# uOsc_2_board_2_v2_0.net
KiCad netlist of a schematic drawn in EAGLE
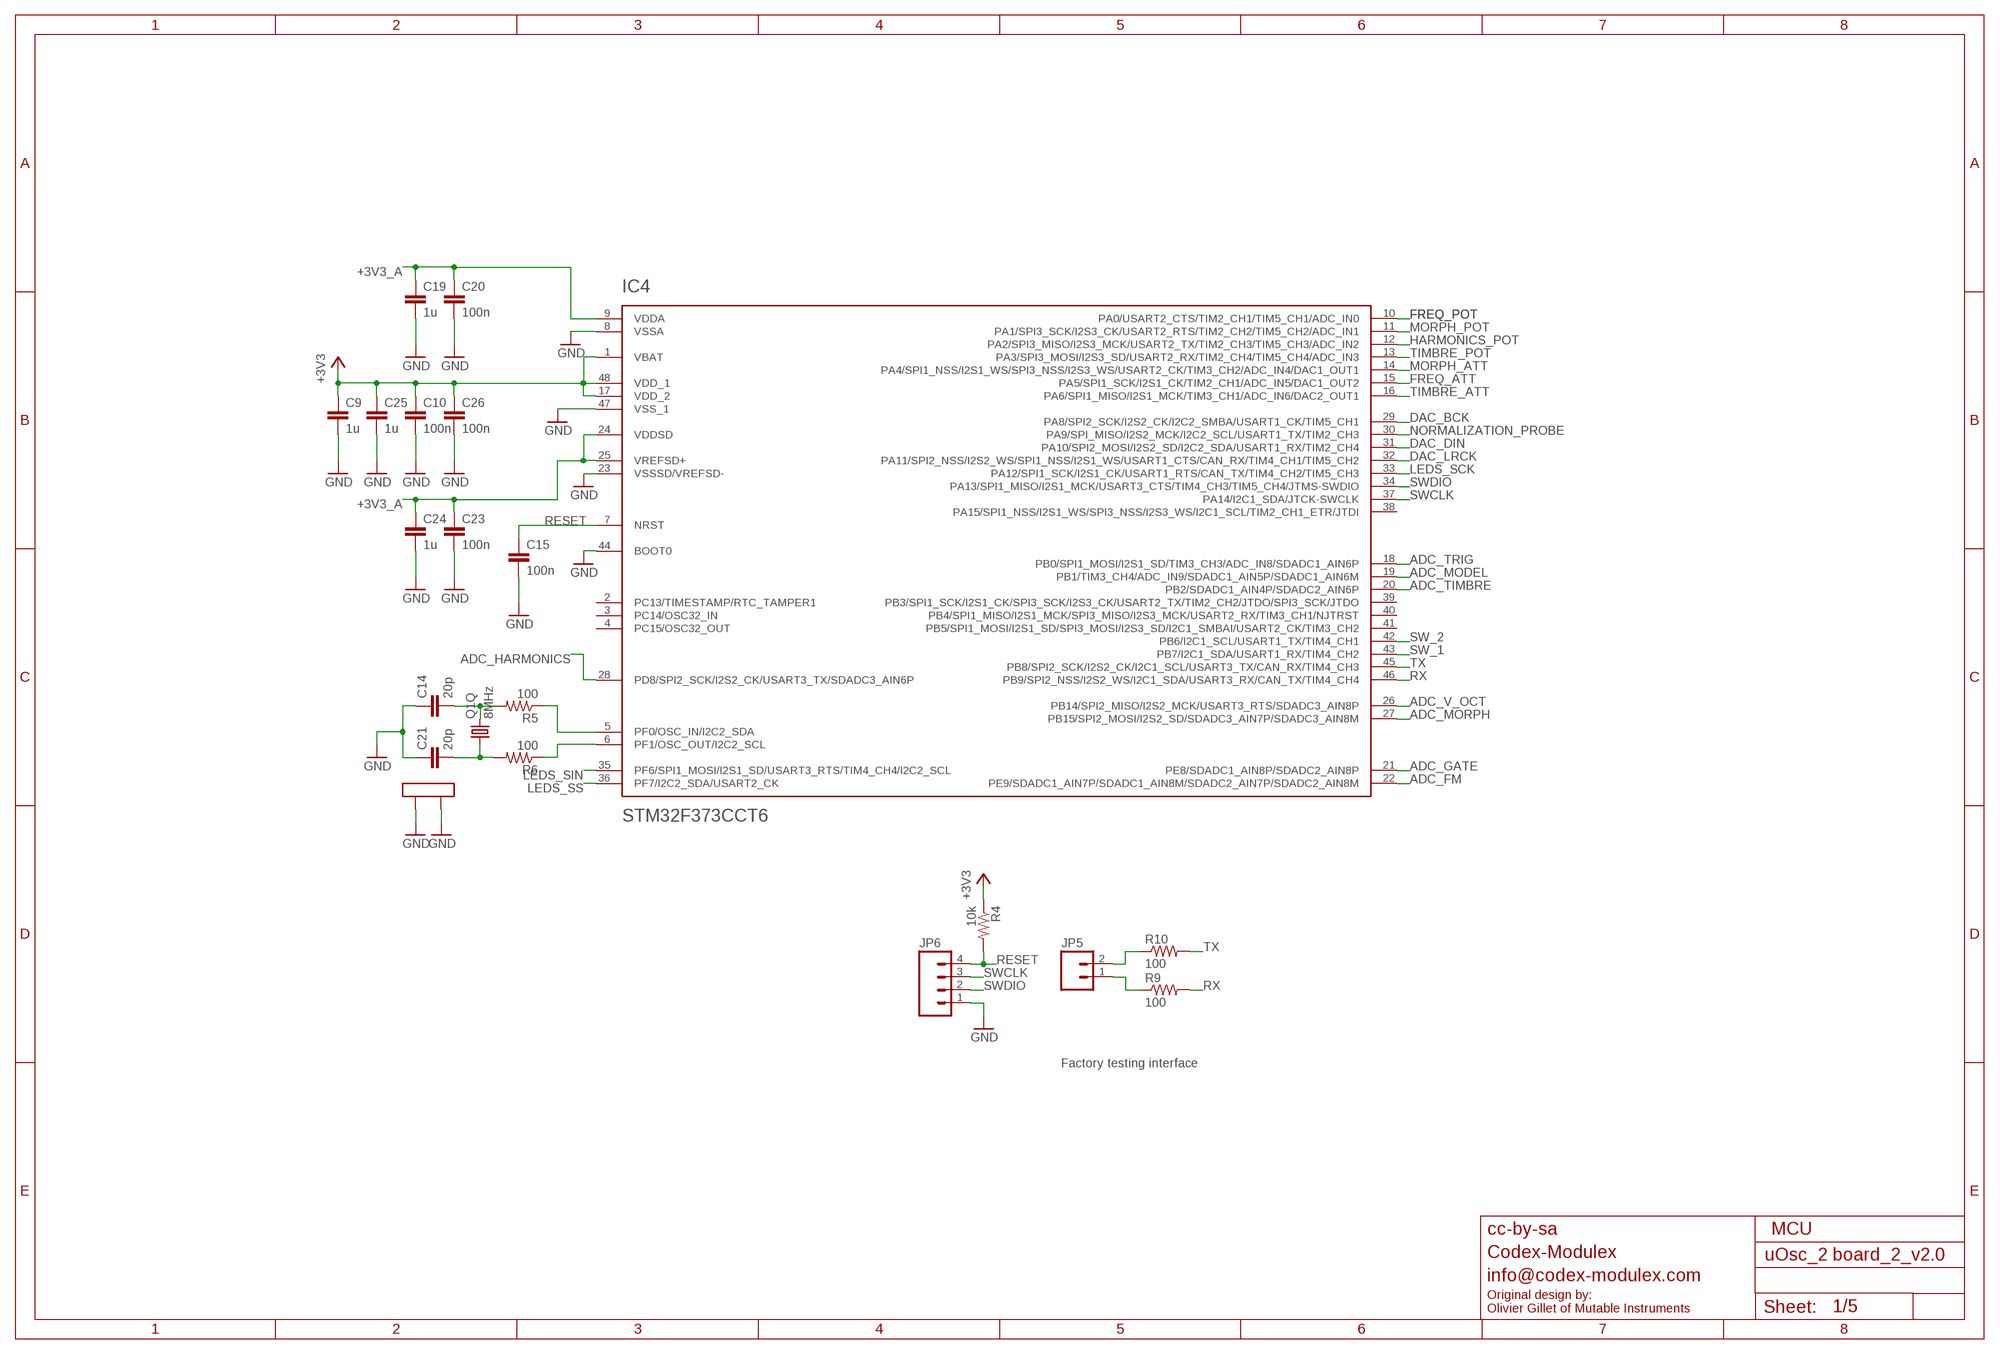
[diagram p0: schematic, sheet 1]
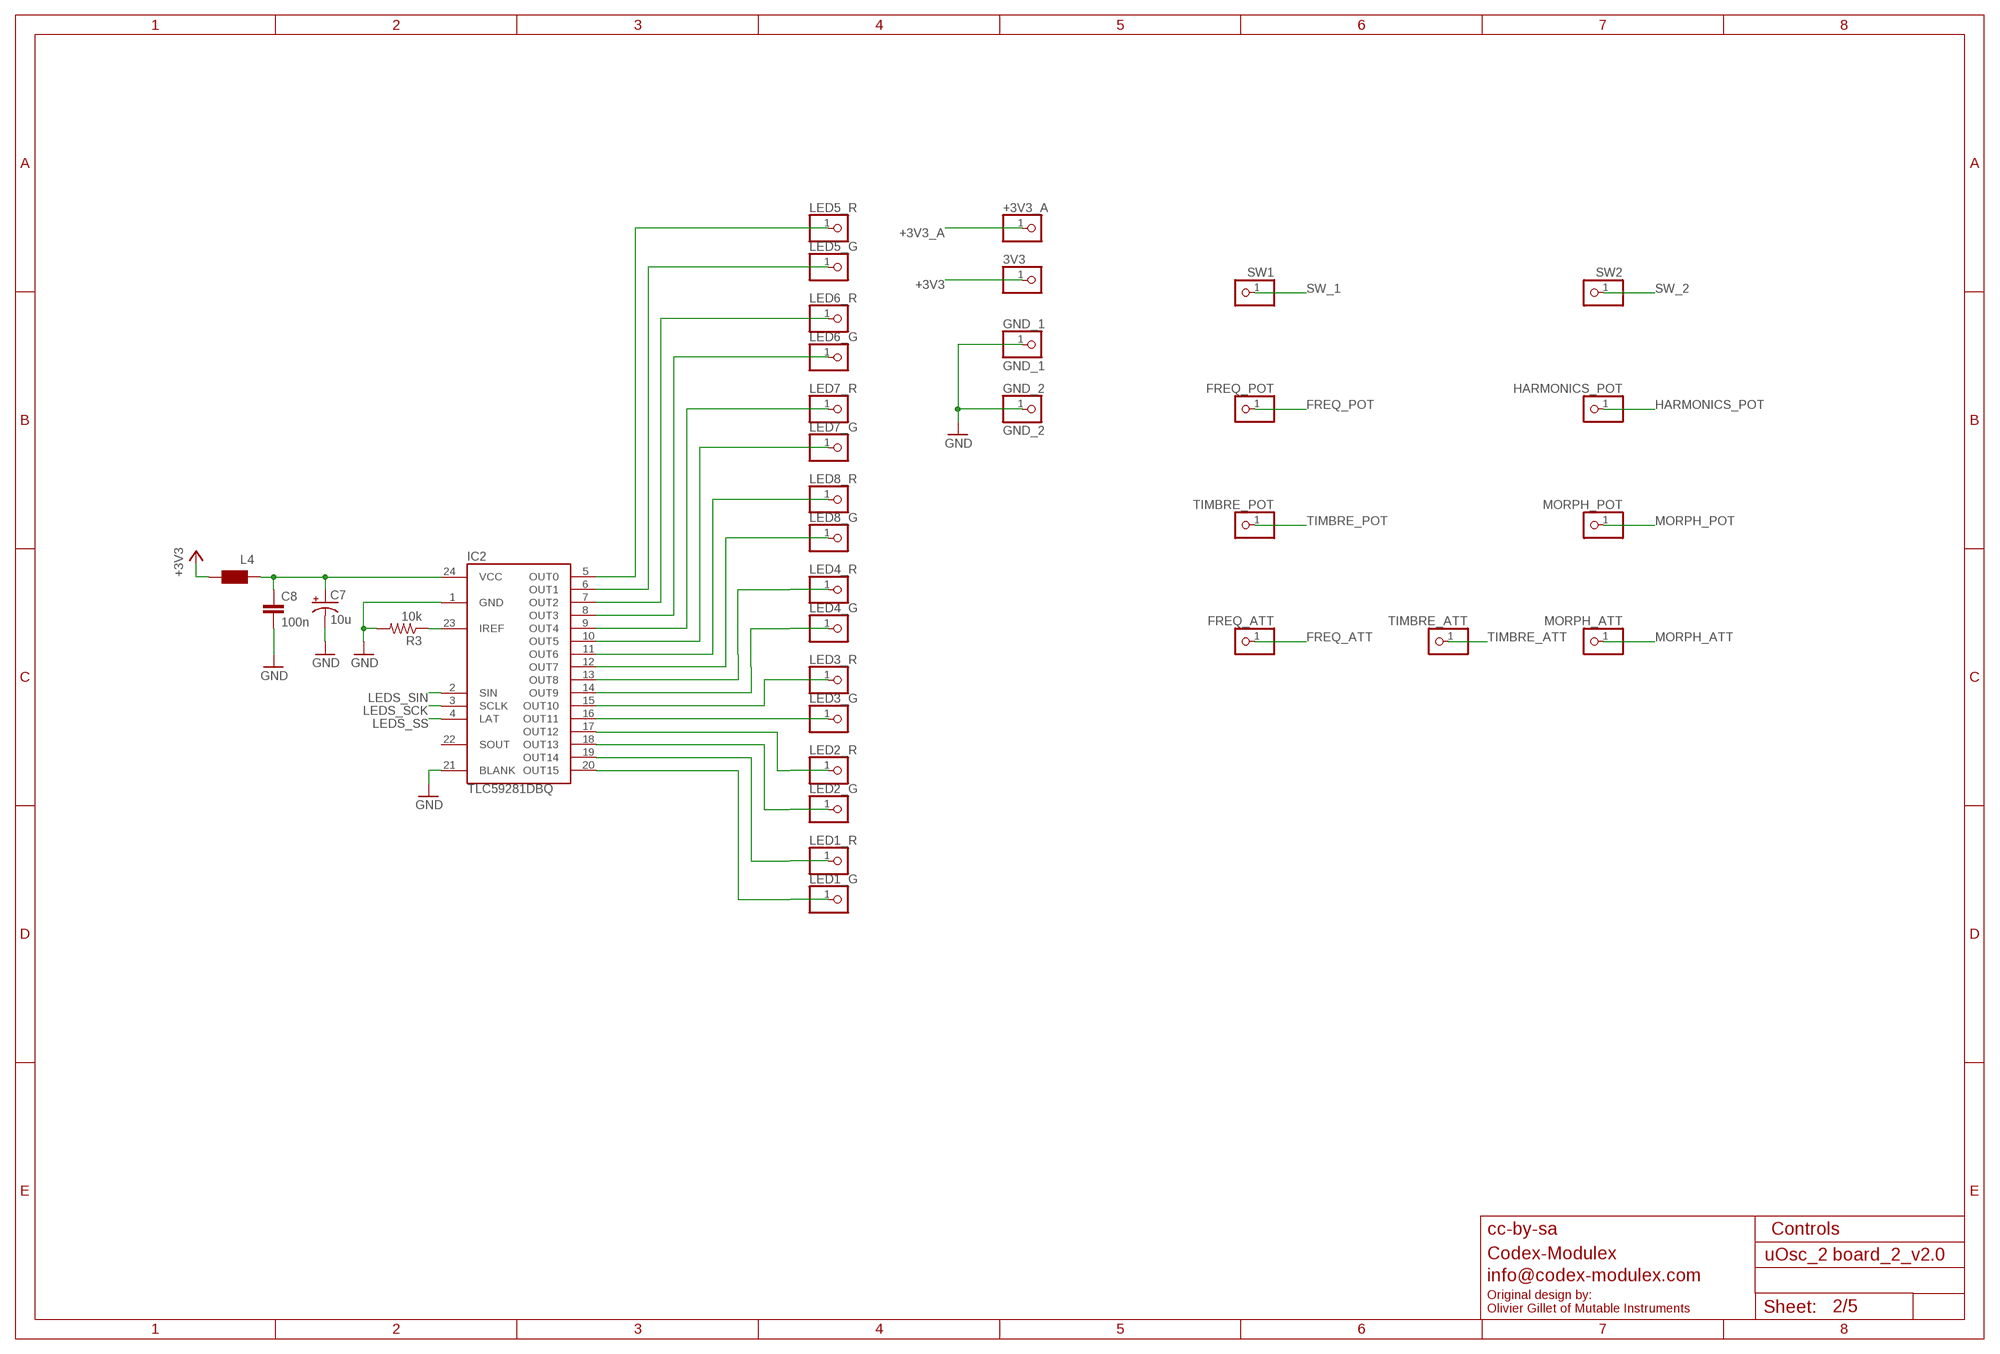
[diagram p1: schematic, sheet 2]
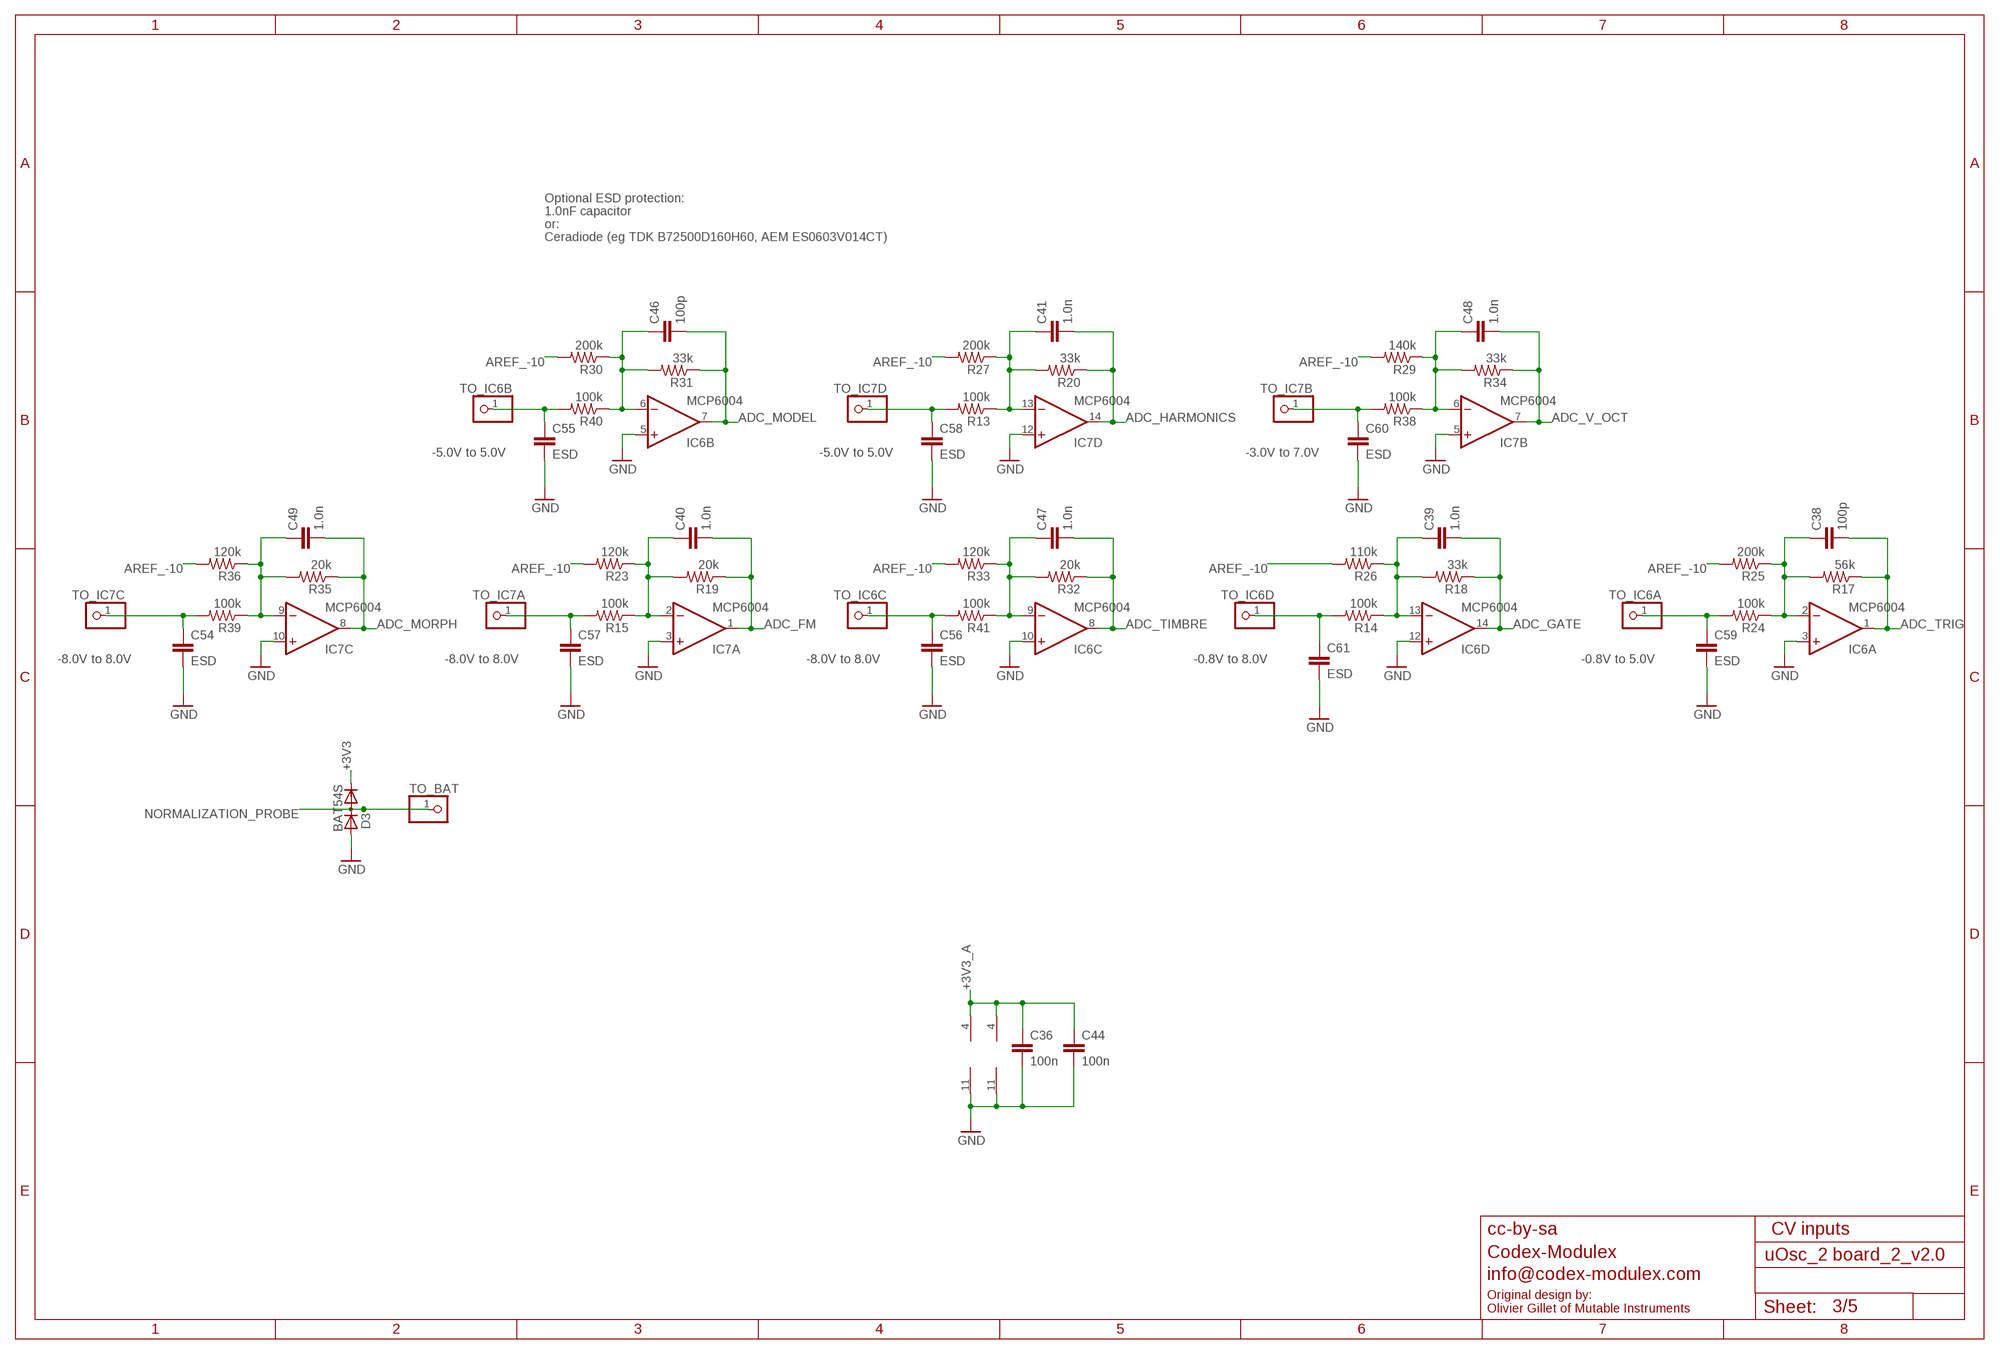
[diagram p2: schematic, sheet 3]
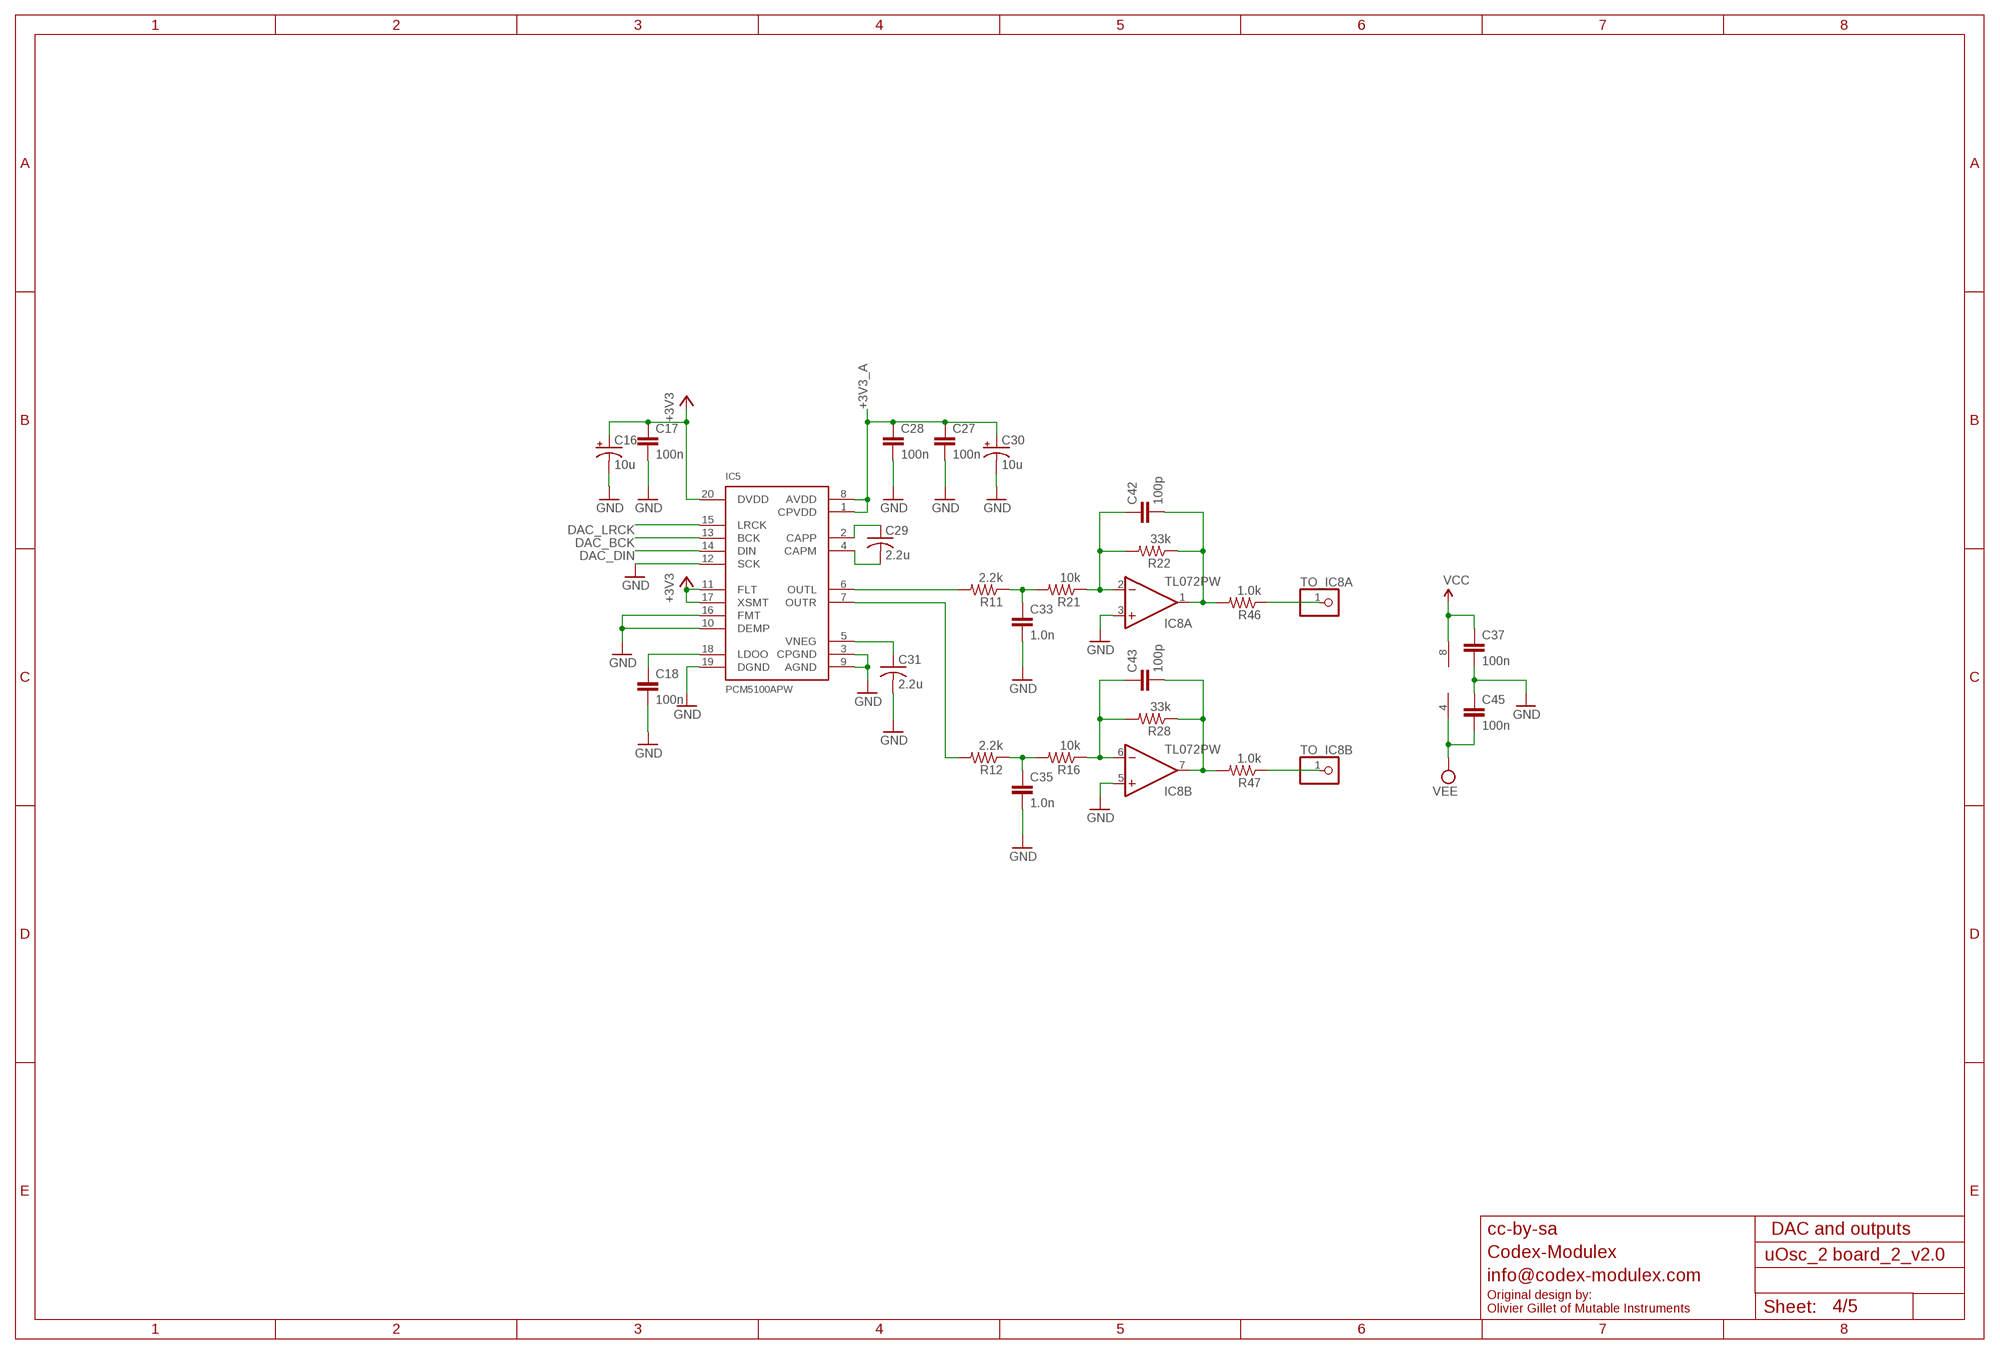
[diagram p3: schematic, sheet 4]
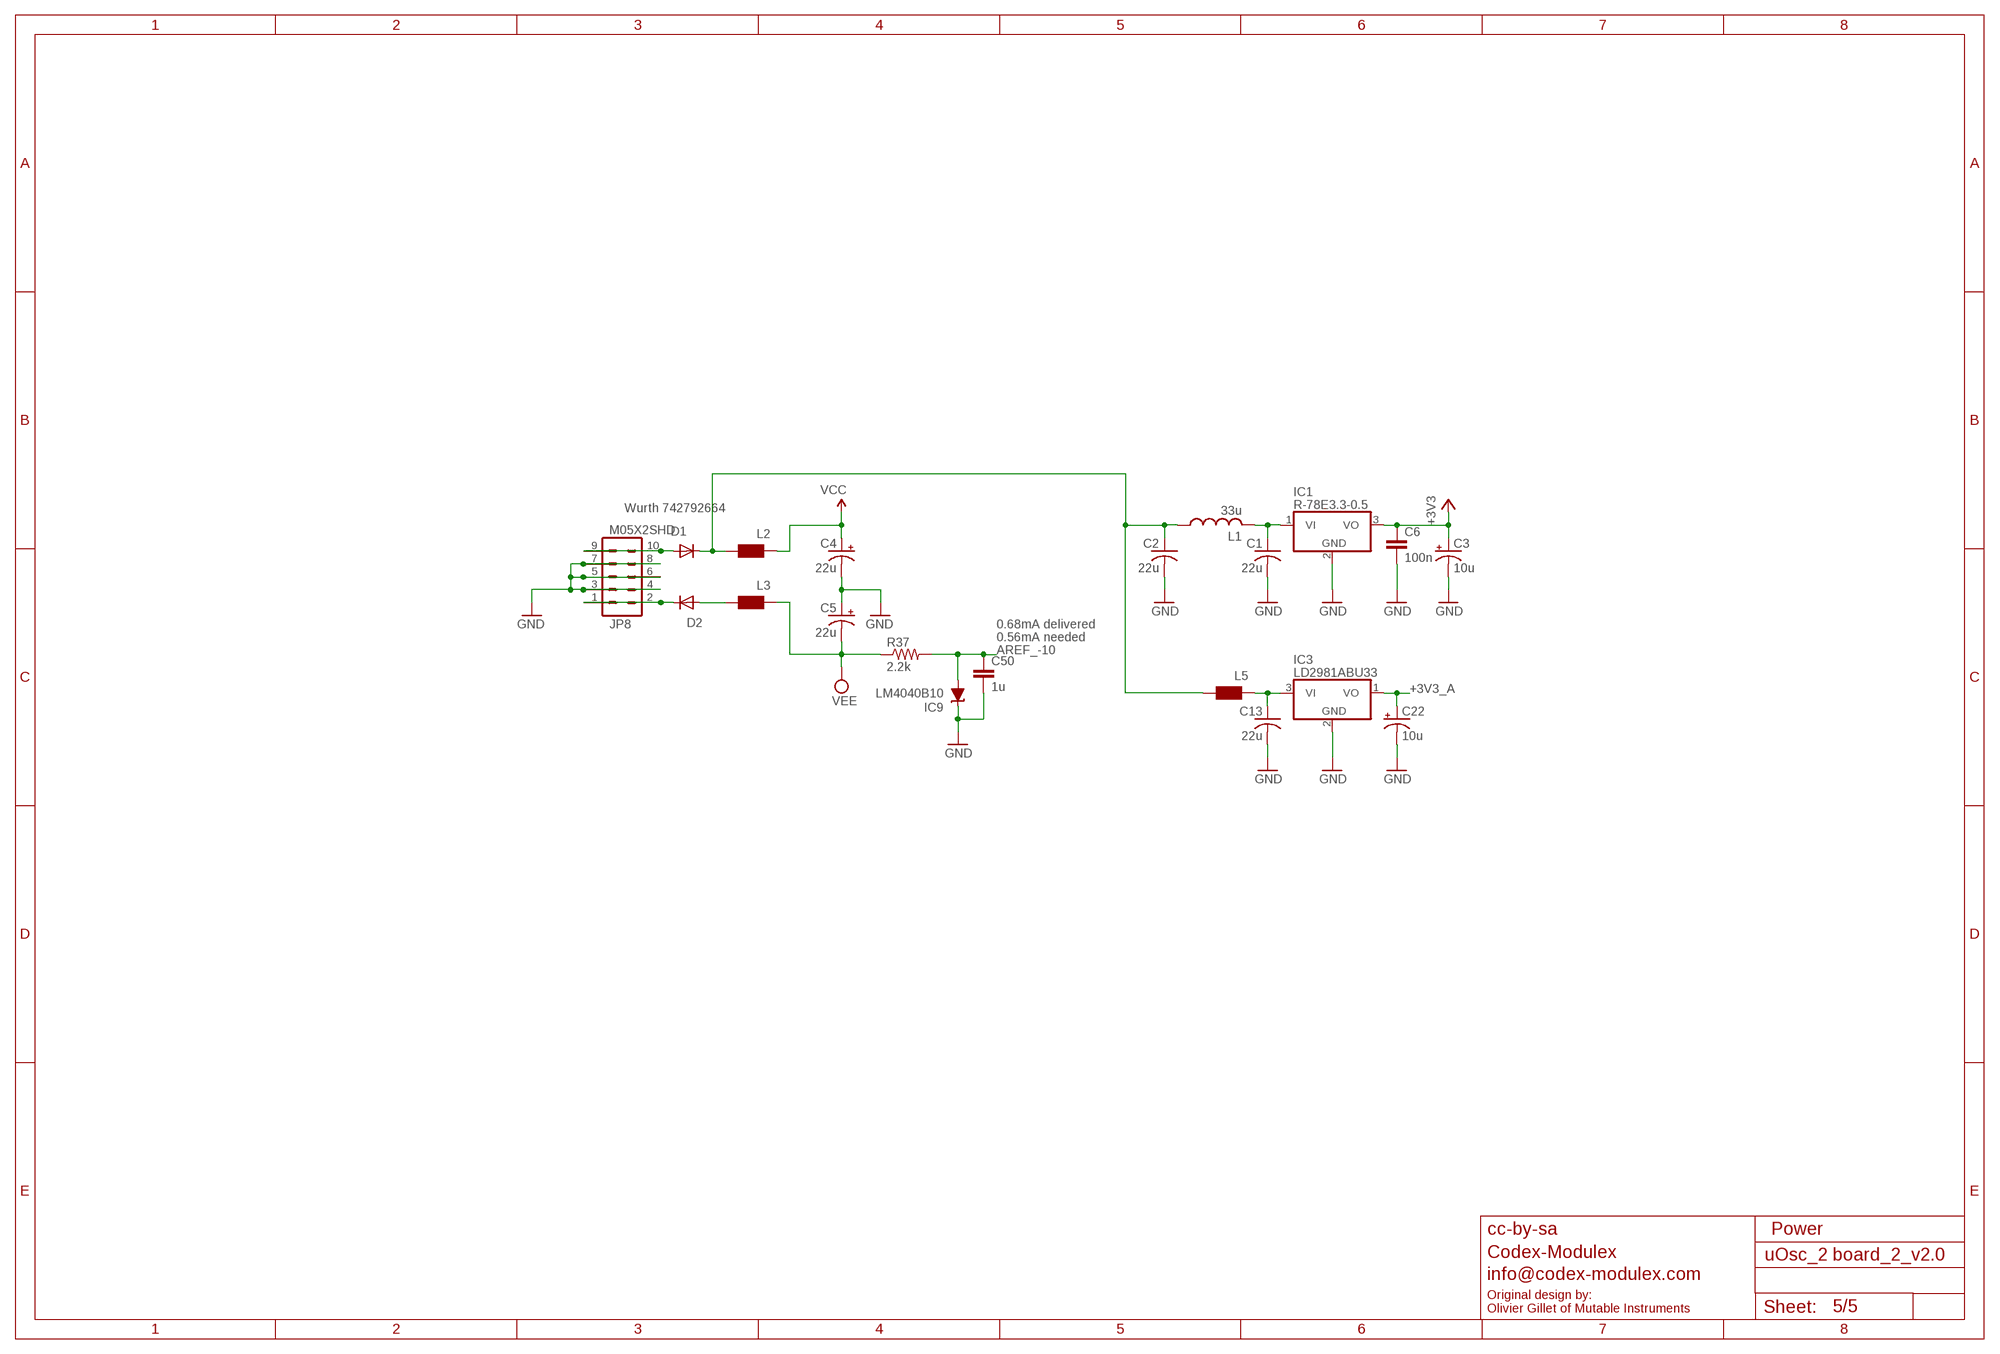
[diagram p4: schematic, sheet 5]

(export (version "E")
  (design (tool "Eeschema 10.0.6"))
  (components
    (comp (ref "C16")
      (value "10u")
      (footprint "eagle-import:PANASONIC_A")
      (libsource (lib "eagle-import") (part "CPOL-USA"))
    )
    (comp (ref "C17")
      (value "100n")
      (footprint "eagle-import:PARTS_AMAN_RESISTOR_0603")
      (libsource (lib "eagle-import") (part "PARTS_AMAN_CAPACITOR"))
    )
    (comp (ref "C18")
      (value "100n")
      (footprint "eagle-import:PARTS_AMAN_RESISTOR_0603")
      (libsource (lib "eagle-import") (part "PARTS_AMAN_CAPACITOR"))
    )
    (comp (ref "C27")
      (value "100n")
      (footprint "eagle-import:PARTS_AMAN_RESISTOR_0603")
      (libsource (lib "eagle-import") (part "PARTS_AMAN_CAPACITOR"))
    )
    (comp (ref "C28")
      (value "100n")
      (footprint "eagle-import:PARTS_AMAN_RESISTOR_0603")
      (libsource (lib "eagle-import") (part "PARTS_AMAN_CAPACITOR"))
    )
    (comp (ref "C29")
      (value "2.2u")
      (footprint "eagle-import:C0805")
      (libsource (lib "eagle-import") (part "C-USC0805"))
    )
    (comp (ref "C30")
      (value "10u")
      (footprint "eagle-import:PANASONIC_A")
      (libsource (lib "eagle-import") (part "CPOL-USA"))
    )
    (comp (ref "C31")
      (value "2.2u")
      (footprint "eagle-import:C0805")
      (libsource (lib "eagle-import") (part "C-USC0805"))
    )
    (comp (ref "C33")
      (value "1.0n")
      (footprint "eagle-import:PARTS_AMAN_RESISTOR_0603")
      (libsource (lib "eagle-import") (part "PARTS_AMAN_CAPACITOR"))
    )
    (comp (ref "C35")
      (value "1.0n")
      (footprint "eagle-import:PARTS_AMAN_RESISTOR_0603")
      (libsource (lib "eagle-import") (part "PARTS_AMAN_CAPACITOR"))
    )
    (comp (ref "C37")
      (value "100n")
      (footprint "eagle-import:PARTS_AMAN_RESISTOR_0603")
      (libsource (lib "eagle-import") (part "PARTS_AMAN_CAPACITOR"))
    )
    (comp (ref "C42")
      (value "100p")
      (footprint "eagle-import:PARTS_AMAN_RESISTOR_0603")
      (libsource (lib "eagle-import") (part "PARTS_AMAN_CAPACITOR"))
    )
    (comp (ref "C43")
      (value "100p")
      (footprint "eagle-import:PARTS_AMAN_RESISTOR_0603")
      (libsource (lib "eagle-import") (part "PARTS_AMAN_CAPACITOR"))
    )
    (comp (ref "C45")
      (value "100n")
      (footprint "eagle-import:PARTS_AMAN_RESISTOR_0603")
      (libsource (lib "eagle-import") (part "PARTS_AMAN_CAPACITOR"))
    )
    (comp (ref "IC5")
      (value "PCM5100APW")
      (footprint "eagle-import:SSOP20")
      (libsource (lib "eagle-import") (part "PCM5100PW"))
    )
    (comp (ref "IC8")
      (value "TL072PW")
      (footprint "eagle-import:TSSOP08")
      (libsource (lib "eagle-import") (part "TL072PW"))
    )
    (comp (ref "R11")
      (value "2.2k")
      (footprint "eagle-import:PARTS_AMAN_RESISTOR_0603")
      (libsource (lib "eagle-import") (part "PARTS_AMAN_RESISTOR"))
    )
    (comp (ref "R12")
      (value "2.2k")
      (footprint "eagle-import:PARTS_AMAN_RESISTOR_0603")
      (libsource (lib "eagle-import") (part "PARTS_AMAN_RESISTOR"))
    )
    (comp (ref "R16")
      (value "10k")
      (footprint "eagle-import:PARTS_AMAN_RESISTOR_0603")
      (libsource (lib "eagle-import") (part "PARTS_AMAN_RESISTOR"))
    )
    (comp (ref "R21")
      (value "10k")
      (footprint "eagle-import:PARTS_AMAN_RESISTOR_0603")
      (libsource (lib "eagle-import") (part "PARTS_AMAN_RESISTOR"))
    )
    (comp (ref "R22")
      (value "33k")
      (footprint "eagle-import:PARTS_AMAN_RESISTOR_0603")
      (libsource (lib "eagle-import") (part "PARTS_AMAN_RESISTOR"))
    )
    (comp (ref "R28")
      (value "33k")
      (footprint "eagle-import:PARTS_AMAN_RESISTOR_0603")
      (libsource (lib "eagle-import") (part "PARTS_AMAN_RESISTOR"))
    )
    (comp (ref "R46")
      (value "1.0k")
      (footprint "eagle-import:PARTS_AMAN_RESISTOR_0603")
      (libsource (lib "eagle-import") (part "PARTS_AMAN_RESISTOR"))
    )
    (comp (ref "R47")
      (value "1.0k")
      (footprint "eagle-import:PARTS_AMAN_RESISTOR_0603")
      (libsource (lib "eagle-import") (part "PARTS_AMAN_RESISTOR"))
    )
    (comp (ref "TO_IC8A")
      (value "PARTS_AMAN_PINHD-1X1")
      (footprint "eagle-import:PARTS_AMAN_1X01")
      (libsource (lib "eagle-import") (part "PARTS_AMAN_PINHD-1X1"))
    )
    (comp (ref "TO_IC8B")
      (value "PARTS_AMAN_PINHD-1X1")
      (footprint "eagle-import:PARTS_AMAN_1X01")
      (libsource (lib "eagle-import") (part "PARTS_AMAN_PINHD-1X1"))
    )
    (comp (ref "C9")
      (value "1u")
      (footprint "eagle-import:PARTS_AMAN_RESISTOR_0603")
      (libsource (lib "eagle-import") (part "PARTS_AMAN_CAPACITOR"))
    )
    (comp (ref "C10")
      (value "100n")
      (footprint "eagle-import:PARTS_AMAN_RESISTOR_0603")
      (libsource (lib "eagle-import") (part "PARTS_AMAN_CAPACITOR"))
    )
    (comp (ref "C14")
      (value "20p")
      (footprint "eagle-import:PARTS_AMAN_RESISTOR_0603")
      (libsource (lib "eagle-import") (part "PARTS_AMAN_CAPACITOR"))
    )
    (comp (ref "C15")
      (value "100n")
      (footprint "eagle-import:PARTS_AMAN_RESISTOR_0603")
      (libsource (lib "eagle-import") (part "PARTS_AMAN_CAPACITOR"))
    )
    (comp (ref "C19")
      (value "1u")
      (footprint "eagle-import:PARTS_AMAN_RESISTOR_0603")
      (libsource (lib "eagle-import") (part "PARTS_AMAN_CAPACITOR"))
    )
    (comp (ref "C20")
      (value "100n")
      (footprint "eagle-import:PARTS_AMAN_RESISTOR_0603")
      (libsource (lib "eagle-import") (part "PARTS_AMAN_CAPACITOR"))
    )
    (comp (ref "C21")
      (value "20p")
      (footprint "eagle-import:PARTS_AMAN_RESISTOR_0603")
      (libsource (lib "eagle-import") (part "PARTS_AMAN_CAPACITOR"))
    )
    (comp (ref "C23")
      (value "100n")
      (footprint "eagle-import:PARTS_AMAN_RESISTOR_0603")
      (libsource (lib "eagle-import") (part "PARTS_AMAN_CAPACITOR"))
    )
    (comp (ref "C24")
      (value "1u")
      (footprint "eagle-import:PARTS_AMAN_RESISTOR_0603")
      (libsource (lib "eagle-import") (part "PARTS_AMAN_CAPACITOR"))
    )
    (comp (ref "C25")
      (value "1u")
      (footprint "eagle-import:PARTS_AMAN_RESISTOR_0603")
      (libsource (lib "eagle-import") (part "PARTS_AMAN_CAPACITOR"))
    )
    (comp (ref "C26")
      (value "100n")
      (footprint "eagle-import:PARTS_AMAN_RESISTOR_0603")
      (libsource (lib "eagle-import") (part "PARTS_AMAN_CAPACITOR"))
    )
    (comp (ref "IC4")
      (value "STM32F373CCT6")
      (footprint "eagle-import:LQFP48")
      (libsource (lib "eagle-import") (part "STM32F373C"))
    )
    (comp (ref "JP5")
      (value "M02PTH")
      (footprint "eagle-import:1X02")
      (libsource (lib "eagle-import") (part "M02PTH"))
    )
    (comp (ref "JP6")
      (value "M04PTH")
      (footprint "eagle-import:1X04")
      (libsource (lib "eagle-import") (part "M04PTH"))
    )
    (comp (ref "Q1")
      (value "8MHz")
      (footprint "eagle-import:CTS406")
      (libsource (lib "eagle-import") (part "CRYSTAL"))
    )
    (comp (ref "R4")
      (value "10k")
      (footprint "eagle-import:PARTS_AMAN_RESISTOR_0603")
      (libsource (lib "eagle-import") (part "PARTS_AMAN_RESISTOR"))
    )
    (comp (ref "R5")
      (value "100")
      (footprint "eagle-import:PARTS_AMAN_RESISTOR_0603")
      (libsource (lib "eagle-import") (part "PARTS_AMAN_RESISTOR"))
    )
    (comp (ref "R6")
      (value "100")
      (footprint "eagle-import:PARTS_AMAN_RESISTOR_0603")
      (libsource (lib "eagle-import") (part "PARTS_AMAN_RESISTOR"))
    )
    (comp (ref "R9")
      (value "100")
      (footprint "eagle-import:PARTS_AMAN_RESISTOR_0603")
      (libsource (lib "eagle-import") (part "PARTS_AMAN_RESISTOR"))
    )
    (comp (ref "R10")
      (value "100")
      (footprint "eagle-import:PARTS_AMAN_RESISTOR_0603")
      (libsource (lib "eagle-import") (part "PARTS_AMAN_RESISTOR"))
    )
    (comp (ref "C36")
      (value "100n")
      (footprint "eagle-import:PARTS_AMAN_RESISTOR_0603")
      (libsource (lib "eagle-import") (part "PARTS_AMAN_CAPACITOR"))
    )
    (comp (ref "C38")
      (value "100p")
      (footprint "eagle-import:PARTS_AMAN_RESISTOR_0603")
      (libsource (lib "eagle-import") (part "PARTS_AMAN_CAPACITOR"))
    )
    (comp (ref "C39")
      (value "1.0n")
      (footprint "eagle-import:PARTS_AMAN_RESISTOR_0603")
      (libsource (lib "eagle-import") (part "PARTS_AMAN_CAPACITOR"))
    )
    (comp (ref "C40")
      (value "1.0n")
      (footprint "eagle-import:PARTS_AMAN_RESISTOR_0603")
      (libsource (lib "eagle-import") (part "PARTS_AMAN_CAPACITOR"))
    )
    (comp (ref "C41")
      (value "1.0n")
      (footprint "eagle-import:PARTS_AMAN_RESISTOR_0603")
      (libsource (lib "eagle-import") (part "PARTS_AMAN_CAPACITOR"))
    )
    (comp (ref "C44")
      (value "100n")
      (footprint "eagle-import:PARTS_AMAN_RESISTOR_0603")
      (libsource (lib "eagle-import") (part "PARTS_AMAN_CAPACITOR"))
    )
    (comp (ref "C46")
      (value "100p")
      (footprint "eagle-import:PARTS_AMAN_RESISTOR_0603")
      (libsource (lib "eagle-import") (part "PARTS_AMAN_CAPACITOR"))
    )
    (comp (ref "C47")
      (value "1.0n")
      (footprint "eagle-import:PARTS_AMAN_RESISTOR_0603")
      (libsource (lib "eagle-import") (part "PARTS_AMAN_CAPACITOR"))
    )
    (comp (ref "C48")
      (value "1.0n")
      (footprint "eagle-import:PARTS_AMAN_RESISTOR_0603")
      (libsource (lib "eagle-import") (part "PARTS_AMAN_CAPACITOR"))
    )
    (comp (ref "C49")
      (value "1.0n")
      (footprint "eagle-import:PARTS_AMAN_RESISTOR_0603")
      (libsource (lib "eagle-import") (part "PARTS_AMAN_CAPACITOR"))
    )
    (comp (ref "C54")
      (value "ESD")
      (footprint "eagle-import:PARTS_AMAN_RESISTOR_0603")
      (libsource (lib "eagle-import") (part "PARTS_AMAN_CAPACITOR"))
    )
    (comp (ref "C55")
      (value "ESD")
      (footprint "eagle-import:PARTS_AMAN_RESISTOR_0603")
      (libsource (lib "eagle-import") (part "PARTS_AMAN_CAPACITOR"))
    )
    (comp (ref "C56")
      (value "ESD")
      (footprint "eagle-import:PARTS_AMAN_RESISTOR_0603")
      (libsource (lib "eagle-import") (part "PARTS_AMAN_CAPACITOR"))
    )
    (comp (ref "C57")
      (value "ESD")
      (footprint "eagle-import:PARTS_AMAN_RESISTOR_0603")
      (libsource (lib "eagle-import") (part "PARTS_AMAN_CAPACITOR"))
    )
    (comp (ref "C58")
      (value "ESD")
      (footprint "eagle-import:PARTS_AMAN_RESISTOR_0603")
      (libsource (lib "eagle-import") (part "PARTS_AMAN_CAPACITOR"))
    )
    (comp (ref "C59")
      (value "ESD")
      (footprint "eagle-import:PARTS_AMAN_RESISTOR_0603")
      (libsource (lib "eagle-import") (part "PARTS_AMAN_CAPACITOR"))
    )
    (comp (ref "C60")
      (value "ESD")
      (footprint "eagle-import:PARTS_AMAN_RESISTOR_0603")
      (libsource (lib "eagle-import") (part "PARTS_AMAN_CAPACITOR"))
    )
    (comp (ref "C61")
      (value "ESD")
      (footprint "eagle-import:PARTS_AMAN_RESISTOR_0603")
      (libsource (lib "eagle-import") (part "PARTS_AMAN_CAPACITOR"))
    )
    (comp (ref "D3")
      (value "BAT54S")
      (footprint "eagle-import:SOT23")
      (libsource (lib "eagle-import") (part "DIODE_2CACA-SOT23"))
    )
    (comp (ref "IC6")
      (value "MCP6004")
      (footprint "eagle-import:TSSOP14_065")
      (libsource (lib "eagle-import") (part "TL074PW"))
    )
    (comp (ref "IC7")
      (value "MCP6004")
      (footprint "eagle-import:TSSOP14_065")
      (libsource (lib "eagle-import") (part "TL074PW"))
    )
    (comp (ref "R13")
      (value "100k")
      (footprint "eagle-import:PARTS_AMAN_RESISTOR_0603")
      (libsource (lib "eagle-import") (part "PARTS_AMAN_RESISTOR"))
    )
    (comp (ref "R14")
      (value "100k")
      (footprint "eagle-import:PARTS_AMAN_RESISTOR_0603")
      (libsource (lib "eagle-import") (part "PARTS_AMAN_RESISTOR"))
    )
    (comp (ref "R15")
      (value "100k")
      (footprint "eagle-import:PARTS_AMAN_RESISTOR_0603")
      (libsource (lib "eagle-import") (part "PARTS_AMAN_RESISTOR"))
    )
    (comp (ref "R17")
      (value "56k")
      (footprint "eagle-import:PARTS_AMAN_RESISTOR_0603")
      (libsource (lib "eagle-import") (part "PARTS_AMAN_RESISTOR"))
    )
    (comp (ref "R18")
      (value "33k")
      (footprint "eagle-import:PARTS_AMAN_RESISTOR_0603")
      (libsource (lib "eagle-import") (part "PARTS_AMAN_RESISTOR"))
    )
    (comp (ref "R19")
      (value "20k")
      (footprint "eagle-import:PARTS_AMAN_RESISTOR_0603")
      (libsource (lib "eagle-import") (part "PARTS_AMAN_RESISTOR"))
    )
    (comp (ref "R20")
      (value "33k")
      (footprint "eagle-import:PARTS_AMAN_RESISTOR_0603")
      (libsource (lib "eagle-import") (part "PARTS_AMAN_RESISTOR"))
    )
    (comp (ref "R23")
      (value "120k")
      (footprint "eagle-import:PARTS_AMAN_RESISTOR_0603")
      (libsource (lib "eagle-import") (part "PARTS_AMAN_RESISTOR"))
    )
    (comp (ref "R24")
      (value "100k")
      (footprint "eagle-import:PARTS_AMAN_RESISTOR_0603")
      (libsource (lib "eagle-import") (part "PARTS_AMAN_RESISTOR"))
    )
    (comp (ref "R25")
      (value "200k")
      (footprint "eagle-import:PARTS_AMAN_RESISTOR_0603")
      (libsource (lib "eagle-import") (part "PARTS_AMAN_RESISTOR"))
    )
    (comp (ref "R26")
      (value "110k")
      (footprint "eagle-import:PARTS_AMAN_RESISTOR_0603")
      (libsource (lib "eagle-import") (part "PARTS_AMAN_RESISTOR"))
    )
    (comp (ref "R27")
      (value "200k")
      (footprint "eagle-import:PARTS_AMAN_RESISTOR_0603")
      (libsource (lib "eagle-import") (part "PARTS_AMAN_RESISTOR"))
    )
    (comp (ref "R29")
      (value "140k")
      (footprint "eagle-import:PARTS_AMAN_RESISTOR_0603")
      (libsource (lib "eagle-import") (part "PARTS_AMAN_RESISTOR"))
    )
    (comp (ref "R30")
      (value "200k")
      (footprint "eagle-import:PARTS_AMAN_RESISTOR_0603")
      (libsource (lib "eagle-import") (part "PARTS_AMAN_RESISTOR"))
    )
    (comp (ref "R31")
      (value "33k")
      (footprint "eagle-import:PARTS_AMAN_RESISTOR_0603")
      (libsource (lib "eagle-import") (part "PARTS_AMAN_RESISTOR"))
    )
    (comp (ref "R32")
      (value "20k")
      (footprint "eagle-import:PARTS_AMAN_RESISTOR_0603")
      (libsource (lib "eagle-import") (part "PARTS_AMAN_RESISTOR"))
    )
    (comp (ref "R33")
      (value "120k")
      (footprint "eagle-import:PARTS_AMAN_RESISTOR_0603")
      (libsource (lib "eagle-import") (part "PARTS_AMAN_RESISTOR"))
    )
    (comp (ref "R34")
      (value "33k")
      (footprint "eagle-import:PARTS_AMAN_RESISTOR_0603")
      (libsource (lib "eagle-import") (part "PARTS_AMAN_RESISTOR"))
    )
    (comp (ref "R35")
      (value "20k")
      (footprint "eagle-import:PARTS_AMAN_RESISTOR_0603")
      (libsource (lib "eagle-import") (part "PARTS_AMAN_RESISTOR"))
    )
    (comp (ref "R36")
      (value "120k")
      (footprint "eagle-import:PARTS_AMAN_RESISTOR_0603")
      (libsource (lib "eagle-import") (part "PARTS_AMAN_RESISTOR"))
    )
    (comp (ref "R38")
      (value "100k")
      (footprint "eagle-import:PARTS_AMAN_RESISTOR_0603")
      (libsource (lib "eagle-import") (part "PARTS_AMAN_RESISTOR"))
    )
    (comp (ref "R39")
      (value "100k")
      (footprint "eagle-import:PARTS_AMAN_RESISTOR_0603")
      (libsource (lib "eagle-import") (part "PARTS_AMAN_RESISTOR"))
    )
    (comp (ref "R40")
      (value "100k")
      (footprint "eagle-import:PARTS_AMAN_RESISTOR_0603")
      (libsource (lib "eagle-import") (part "PARTS_AMAN_RESISTOR"))
    )
    (comp (ref "R41")
      (value "100k")
      (footprint "eagle-import:PARTS_AMAN_RESISTOR_0603")
      (libsource (lib "eagle-import") (part "PARTS_AMAN_RESISTOR"))
    )
    (comp (ref "TO_BAT")
      (value "PARTS_AMAN_PINHD-1X1")
      (footprint "eagle-import:PARTS_AMAN_1X01")
      (libsource (lib "eagle-import") (part "PARTS_AMAN_PINHD-1X1"))
    )
    (comp (ref "TO_IC6A")
      (value "PARTS_AMAN_PINHD-1X1")
      (footprint "eagle-import:PARTS_AMAN_1X01")
      (libsource (lib "eagle-import") (part "PARTS_AMAN_PINHD-1X1"))
    )
    (comp (ref "TO_IC6B")
      (value "PARTS_AMAN_PINHD-1X1")
      (footprint "eagle-import:PARTS_AMAN_1X01")
      (libsource (lib "eagle-import") (part "PARTS_AMAN_PINHD-1X1"))
    )
    (comp (ref "TO_IC6C")
      (value "PARTS_AMAN_PINHD-1X1")
      (footprint "eagle-import:PARTS_AMAN_1X01")
      (libsource (lib "eagle-import") (part "PARTS_AMAN_PINHD-1X1"))
    )
    (comp (ref "TO_IC6D")
      (value "PARTS_AMAN_PINHD-1X1")
      (footprint "eagle-import:PARTS_AMAN_1X01")
      (libsource (lib "eagle-import") (part "PARTS_AMAN_PINHD-1X1"))
    )
    (comp (ref "TO_IC7A")
      (value "PARTS_AMAN_PINHD-1X1")
      (footprint "eagle-import:PARTS_AMAN_1X01")
      (libsource (lib "eagle-import") (part "PARTS_AMAN_PINHD-1X1"))
    )
    (comp (ref "TO_IC7B")
      (value "PARTS_AMAN_PINHD-1X1")
      (footprint "eagle-import:PARTS_AMAN_1X01")
      (libsource (lib "eagle-import") (part "PARTS_AMAN_PINHD-1X1"))
    )
    (comp (ref "TO_IC7C")
      (value "PARTS_AMAN_PINHD-1X1")
      (footprint "eagle-import:PARTS_AMAN_1X01")
      (libsource (lib "eagle-import") (part "PARTS_AMAN_PINHD-1X1"))
    )
    (comp (ref "TO_IC7D")
      (value "PARTS_AMAN_PINHD-1X1")
      (footprint "eagle-import:PARTS_AMAN_1X01")
      (libsource (lib "eagle-import") (part "PARTS_AMAN_PINHD-1X1"))
    )
    (comp (ref "+3V3_A")
      (value "PARTS_AMAN_PINHD-1X1")
      (footprint "eagle-import:PARTS_AMAN_1X01")
      (libsource (lib "eagle-import") (part "PARTS_AMAN_PINHD-1X1"))
    )
    (comp (ref "3V3")
      (value "PARTS_AMAN_PINHD-1X1")
      (footprint "eagle-import:PARTS_AMAN_1X01")
      (libsource (lib "eagle-import") (part "PARTS_AMAN_PINHD-1X1"))
    )
    (comp (ref "C7")
      (value "10u")
      (footprint "eagle-import:PANASONIC_A")
      (libsource (lib "eagle-import") (part "CPOL-USA"))
    )
    (comp (ref "C8")
      (value "100n")
      (footprint "eagle-import:PARTS_AMAN_RESISTOR_0603")
      (libsource (lib "eagle-import") (part "PARTS_AMAN_CAPACITOR"))
    )
    (comp (ref "FREQ_ATT")
      (value "PARTS_AMAN_PINHD-1X1")
      (footprint "eagle-import:PARTS_AMAN_1X01")
      (libsource (lib "eagle-import") (part "PARTS_AMAN_PINHD-1X1"))
    )
    (comp (ref "FREQ_POT")
      (value "PARTS_AMAN_PINHD-1X1")
      (footprint "eagle-import:PARTS_AMAN_1X01")
      (libsource (lib "eagle-import") (part "PARTS_AMAN_PINHD-1X1"))
    )
    (comp (ref "GND_1")
      (value "GND_1")
      (footprint "eagle-import:PARTS_AMAN_1X01")
      (libsource (lib "eagle-import") (part "PARTS_AMAN_PINHD-1X1"))
    )
    (comp (ref "GND_2")
      (value "GND_2")
      (footprint "eagle-import:PARTS_AMAN_1X01")
      (libsource (lib "eagle-import") (part "PARTS_AMAN_PINHD-1X1"))
    )
    (comp (ref "HARMONICS_POT")
      (value "PARTS_AMAN_PINHD-1X1")
      (footprint "eagle-import:PARTS_AMAN_1X01")
      (libsource (lib "eagle-import") (part "PARTS_AMAN_PINHD-1X1"))
    )
    (comp (ref "IC2")
      (value "TLC59281DBQ")
      (footprint "eagle-import:TSSOP24_0635")
      (libsource (lib "eagle-import") (part "TLC59281DBQ"))
    )
    (comp (ref "L4")
      (value "WE-CBF_0603")
      (footprint "eagle-import:0603")
      (libsource (lib "eagle-import") (part "WE-CBF_0603"))
    )
    (comp (ref "LED1_G")
      (value "PARTS_AMAN_PINHD-1X1")
      (footprint "eagle-import:PARTS_AMAN_1X01")
      (libsource (lib "eagle-import") (part "PARTS_AMAN_PINHD-1X1"))
    )
    (comp (ref "LED1_R")
      (value "PARTS_AMAN_PINHD-1X1")
      (footprint "eagle-import:PARTS_AMAN_1X01")
      (libsource (lib "eagle-import") (part "PARTS_AMAN_PINHD-1X1"))
    )
    (comp (ref "LED2_G")
      (value "PARTS_AMAN_PINHD-1X1")
      (footprint "eagle-import:PARTS_AMAN_1X01")
      (libsource (lib "eagle-import") (part "PARTS_AMAN_PINHD-1X1"))
    )
    (comp (ref "LED2_R")
      (value "PARTS_AMAN_PINHD-1X1")
      (footprint "eagle-import:PARTS_AMAN_1X01")
      (libsource (lib "eagle-import") (part "PARTS_AMAN_PINHD-1X1"))
    )
    (comp (ref "LED3_G")
      (value "PARTS_AMAN_PINHD-1X1")
      (footprint "eagle-import:PARTS_AMAN_1X01")
      (libsource (lib "eagle-import") (part "PARTS_AMAN_PINHD-1X1"))
    )
    (comp (ref "LED3_R")
      (value "PARTS_AMAN_PINHD-1X1")
      (footprint "eagle-import:PARTS_AMAN_1X01")
      (libsource (lib "eagle-import") (part "PARTS_AMAN_PINHD-1X1"))
    )
    (comp (ref "LED4_G")
      (value "PARTS_AMAN_PINHD-1X1")
      (footprint "eagle-import:PARTS_AMAN_1X01")
      (libsource (lib "eagle-import") (part "PARTS_AMAN_PINHD-1X1"))
    )
    (comp (ref "LED4_R")
      (value "PARTS_AMAN_PINHD-1X1")
      (footprint "eagle-import:PARTS_AMAN_1X01")
      (libsource (lib "eagle-import") (part "PARTS_AMAN_PINHD-1X1"))
    )
    (comp (ref "LED5_G")
      (value "PARTS_AMAN_PINHD-1X1")
      (footprint "eagle-import:PARTS_AMAN_1X01")
      (libsource (lib "eagle-import") (part "PARTS_AMAN_PINHD-1X1"))
    )
    (comp (ref "LED5_R")
      (value "PARTS_AMAN_PINHD-1X1")
      (footprint "eagle-import:PARTS_AMAN_1X01")
      (libsource (lib "eagle-import") (part "PARTS_AMAN_PINHD-1X1"))
    )
    (comp (ref "LED6_G")
      (value "PARTS_AMAN_PINHD-1X1")
      (footprint "eagle-import:PARTS_AMAN_1X01")
      (libsource (lib "eagle-import") (part "PARTS_AMAN_PINHD-1X1"))
    )
    (comp (ref "LED6_R")
      (value "PARTS_AMAN_PINHD-1X1")
      (footprint "eagle-import:PARTS_AMAN_1X01")
      (libsource (lib "eagle-import") (part "PARTS_AMAN_PINHD-1X1"))
    )
    (comp (ref "LED7_G")
      (value "PARTS_AMAN_PINHD-1X1")
      (footprint "eagle-import:PARTS_AMAN_1X01")
      (libsource (lib "eagle-import") (part "PARTS_AMAN_PINHD-1X1"))
    )
    (comp (ref "LED7_R")
      (value "PARTS_AMAN_PINHD-1X1")
      (footprint "eagle-import:PARTS_AMAN_1X01")
      (libsource (lib "eagle-import") (part "PARTS_AMAN_PINHD-1X1"))
    )
    (comp (ref "LED8_G")
      (value "PARTS_AMAN_PINHD-1X1")
      (footprint "eagle-import:PARTS_AMAN_1X01")
      (libsource (lib "eagle-import") (part "PARTS_AMAN_PINHD-1X1"))
    )
    (comp (ref "LED8_R")
      (value "PARTS_AMAN_PINHD-1X1")
      (footprint "eagle-import:PARTS_AMAN_1X01")
      (libsource (lib "eagle-import") (part "PARTS_AMAN_PINHD-1X1"))
    )
    (comp (ref "MORPH_ATT")
      (value "PARTS_AMAN_PINHD-1X1")
      (footprint "eagle-import:PARTS_AMAN_1X01")
      (libsource (lib "eagle-import") (part "PARTS_AMAN_PINHD-1X1"))
    )
    (comp (ref "MORPH_POT")
      (value "PARTS_AMAN_PINHD-1X1")
      (footprint "eagle-import:PARTS_AMAN_1X01")
      (libsource (lib "eagle-import") (part "PARTS_AMAN_PINHD-1X1"))
    )
    (comp (ref "R3")
      (value "10k")
      (footprint "eagle-import:PARTS_AMAN_RESISTOR_0603")
      (libsource (lib "eagle-import") (part "PARTS_AMAN_RESISTOR"))
    )
    (comp (ref "SW1")
      (value "PARTS_AMAN_PINHD-1X1")
      (footprint "eagle-import:PARTS_AMAN_1X01")
      (libsource (lib "eagle-import") (part "PARTS_AMAN_PINHD-1X1"))
    )
    (comp (ref "SW2")
      (value "PARTS_AMAN_PINHD-1X1")
      (footprint "eagle-import:PARTS_AMAN_1X01")
      (libsource (lib "eagle-import") (part "PARTS_AMAN_PINHD-1X1"))
    )
    (comp (ref "TIMBRE_ATT")
      (value "PARTS_AMAN_PINHD-1X1")
      (footprint "eagle-import:PARTS_AMAN_1X01")
      (libsource (lib "eagle-import") (part "PARTS_AMAN_PINHD-1X1"))
    )
    (comp (ref "TIMBRE_POT")
      (value "PARTS_AMAN_PINHD-1X1")
      (footprint "eagle-import:PARTS_AMAN_1X01")
      (libsource (lib "eagle-import") (part "PARTS_AMAN_PINHD-1X1"))
    )
    (comp (ref "C1")
      (value "22u")
      (footprint "eagle-import:C1206")
      (libsource (lib "eagle-import") (part "C-USC1206"))
    )
    (comp (ref "C2")
      (value "22u")
      (footprint "eagle-import:C1206")
      (libsource (lib "eagle-import") (part "C-USC1206"))
    )
    (comp (ref "C3")
      (value "10u")
      (footprint "eagle-import:PANASONIC_A")
      (libsource (lib "eagle-import") (part "CPOL-USA"))
    )
    (comp (ref "C4")
      (value "22u")
      (footprint "eagle-import:PANASONIC_B")
      (libsource (lib "eagle-import") (part "CPOL-USB"))
    )
    (comp (ref "C5")
      (value "22u")
      (footprint "eagle-import:PANASONIC_B")
      (libsource (lib "eagle-import") (part "CPOL-USB"))
    )
    (comp (ref "C6")
      (value "100n")
      (footprint "eagle-import:PARTS_AMAN_RESISTOR_0603")
      (libsource (lib "eagle-import") (part "PARTS_AMAN_CAPACITOR"))
    )
    (comp (ref "C13")
      (value "22u")
      (footprint "eagle-import:C1206")
      (libsource (lib "eagle-import") (part "C-USC1206"))
    )
    (comp (ref "C22")
      (value "10u")
      (footprint "eagle-import:PANASONIC_A")
      (libsource (lib "eagle-import") (part "CPOL-USA"))
    )
    (comp (ref "C50")
      (value "1u")
      (footprint "eagle-import:PARTS_AMAN_RESISTOR_0603")
      (libsource (lib "eagle-import") (part "PARTS_AMAN_CAPACITOR"))
    )
    (comp (ref "D1")
      (value "1N5819HW")
      (footprint "eagle-import:SOD123")
      (libsource (lib "eagle-import") (part "DIODE-SOD123"))
    )
    (comp (ref "D2")
      (value "1N5819HW")
      (footprint "eagle-import:SOD123")
      (libsource (lib "eagle-import") (part "DIODE-SOD123"))
    )
    (comp (ref "IC1")
      (value "R-78E3.3-0.5")
      (footprint "eagle-import:WE78")
      (libsource (lib "eagle-import") (part "WE173950378"))
    )
    (comp (ref "IC3")
      (value "LD2981ABU33")
      (footprint "eagle-import:SOT89")
      (libsource (lib "eagle-import") (part "LD2981ABU"))
    )
    (comp (ref "IC9")
      (value "LM4040B10")
      (footprint "eagle-import:DBZ_R-PDSO-G3")
      (libsource (lib "eagle-import") (part "LM4041DBZB12"))
    )
    (comp (ref "JP8")
      (value "M05X2SHD")
      (footprint "eagle-import:2X5-SHROUDED")
      (libsource (lib "eagle-import") (part "M05X2SHD"))
    )
    (comp (ref "L1")
      (value "33u")
      (footprint "eagle-import:L2012C")
      (libsource (lib "eagle-import") (part "L-USL2012C"))
    )
    (comp (ref "L2")
      (value "WE-CBF_0603")
      (footprint "eagle-import:0603")
      (libsource (lib "eagle-import") (part "WE-CBF_0603"))
    )
    (comp (ref "L3")
      (value "WE-CBF_0603")
      (footprint "eagle-import:0603")
      (libsource (lib "eagle-import") (part "WE-CBF_0603"))
    )
    (comp (ref "L5")
      (value "WE-CBF_0603")
      (footprint "eagle-import:0603")
      (libsource (lib "eagle-import") (part "WE-CBF_0603"))
    )
    (comp (ref "R37")
      (value "2.2k")
      (footprint "eagle-import:PARTS_AMAN_RESISTOR_0603")
      (libsource (lib "eagle-import") (part "PARTS_AMAN_RESISTOR"))
    )
  )
  (nets
    (net (code "1") (name "+3V3") (class "Default")
      (node (ref "3V3") (pin "1") (pinfunction "1_1") (pintype "passive"))
      (node (ref "C10") (pin "1") (pinfunction "1_1") (pintype "passive"))
      (node (ref "C16") (pin "+") (pinfunction "+_+") (pintype "passive"))
      (node (ref "C17") (pin "1") (pinfunction "1_1") (pintype "passive"))
      (node (ref "C25") (pin "1") (pinfunction "1_1") (pintype "passive"))
      (node (ref "C26") (pin "1") (pinfunction "1_1") (pintype "passive"))
      (node (ref "C3") (pin "+") (pinfunction "+_+") (pintype "passive"))
      (node (ref "C6") (pin "1") (pinfunction "1_1") (pintype "passive"))
      (node (ref "C9") (pin "1") (pinfunction "1_1") (pintype "passive"))
      (node (ref "D3") (pin "2") (pinfunction "C_2") (pintype "passive"))
      (node (ref "IC1") (pin "3") (pinfunction "VO_3") (pintype "passive"))
      (node (ref "IC4") (pin "1") (pinfunction "VBAT_1") (pintype "power_in"))
      (node (ref "IC4") (pin "17") (pinfunction "VDD_2_17") (pintype "power_in"))
      (node (ref "IC4") (pin "48") (pinfunction "VDD_1_48") (pintype "power_in"))
      (node (ref "IC5") (pin "11") (pinfunction "FLT_11") (pintype "input"))
      (node (ref "IC5") (pin "17") (pinfunction "XSMT_17") (pintype "input"))
      (node (ref "IC5") (pin "20") (pinfunction "DVDD_20") (pintype "power_in"))
      (node (ref "L4") (pin "2") (pinfunction "2_2") (pintype "passive"))
      (node (ref "R4") (pin "1") (pinfunction "1_1") (pintype "passive"))
    )
    (net (code "2") (name "+3V3_A") (class "Default")
      (node (ref "+3V3_A") (pin "1") (pinfunction "1_1") (pintype "passive"))
      (node (ref "C19") (pin "1") (pinfunction "1_1") (pintype "passive"))
      (node (ref "C20") (pin "1") (pinfunction "1_1") (pintype "passive"))
      (node (ref "C22") (pin "+") (pinfunction "+_+") (pintype "passive"))
      (node (ref "C23") (pin "1") (pinfunction "1_1") (pintype "passive"))
      (node (ref "C24") (pin "1") (pinfunction "1_1") (pintype "passive"))
      (node (ref "C27") (pin "1") (pinfunction "1_1") (pintype "passive"))
      (node (ref "C28") (pin "1") (pinfunction "1_1") (pintype "passive"))
      (node (ref "C30") (pin "+") (pinfunction "+_+") (pintype "passive"))
      (node (ref "C36") (pin "1") (pinfunction "1_1") (pintype "passive"))
      (node (ref "C44") (pin "1") (pinfunction "1_1") (pintype "passive"))
      (node (ref "IC3") (pin "1") (pinfunction "VO_1") (pintype "passive"))
      (node (ref "IC4") (pin "24") (pinfunction "VDDSD_24") (pintype "power_in"))
      (node (ref "IC4") (pin "25") (pinfunction "VREFSD+_25") (pintype "power_in"))
      (node (ref "IC4") (pin "9") (pinfunction "VDDA_9") (pintype "power_in"))
      (node (ref "IC5") (pin "1") (pinfunction "CPVDD_1") (pintype "bidirectional"))
      (node (ref "IC5") (pin "8") (pinfunction "AVDD_8") (pintype "power_in"))
      (node (ref "IC6") (pin "4") (pinfunction "V+_4") (pintype "power_in"))
      (node (ref "IC7") (pin "4") (pinfunction "V+_4") (pintype "power_in"))
    )
    (net (code "3") (name "ADC_FM") (class "Default")
      (node (ref "C40") (pin "2") (pinfunction "2_2") (pintype "passive"))
      (node (ref "IC4") (pin "22") (pinfunction "PE9/SDADC1_AIN7P/SDADC1_AIN8M/SDADC2_AIN7P/SDADC2_AIN8M_22") (pintype "bidirectional"))
      (node (ref "IC7") (pin "1") (pinfunction "OUT_1") (pintype "output"))
      (node (ref "R19") (pin "1") (pinfunction "1_1") (pintype "passive"))
    )
    (net (code "4") (name "ADC_GATE") (class "Default")
      (node (ref "C39") (pin "2") (pinfunction "2_2") (pintype "passive"))
      (node (ref "IC4") (pin "21") (pinfunction "PE8/SDADC1_AIN8P/SDADC2_AIN8P_21") (pintype "bidirectional"))
      (node (ref "IC6") (pin "14") (pinfunction "OUT_14") (pintype "output"))
      (node (ref "R18") (pin "1") (pinfunction "1_1") (pintype "passive"))
    )
    (net (code "5") (name "ADC_HARMONICS") (class "Default")
      (node (ref "C41") (pin "2") (pinfunction "2_2") (pintype "passive"))
      (node (ref "IC4") (pin "28") (pinfunction "PD8/SPI2_SCK/I2S2_CK/USART3_TX/SDADC3_AIN6P_28") (pintype "bidirectional"))
      (node (ref "IC7") (pin "14") (pinfunction "OUT_14") (pintype "output"))
      (node (ref "R20") (pin "1") (pinfunction "1_1") (pintype "passive"))
    )
    (net (code "6") (name "ADC_MODEL") (class "Default")
      (node (ref "C46") (pin "2") (pinfunction "2_2") (pintype "passive"))
      (node (ref "IC4") (pin "19") (pinfunction "PB1/TIM3_CH4/ADC_IN9/SDADC1_AIN5P/SDADC1_AIN6M_19") (pintype "bidirectional"))
      (node (ref "IC6") (pin "7") (pinfunction "OUT_7") (pintype "output"))
      (node (ref "R31") (pin "1") (pinfunction "1_1") (pintype "passive"))
    )
    (net (code "7") (name "ADC_MORPH") (class "Default")
      (node (ref "C49") (pin "2") (pinfunction "2_2") (pintype "passive"))
      (node (ref "IC4") (pin "27") (pinfunction "PB15/SPI2_MOSI/I2S2_SD/SDADC3_AIN7P/SDADC3_AIN8M_27") (pintype "bidirectional"))
      (node (ref "IC7") (pin "8") (pinfunction "OUT_8") (pintype "output"))
      (node (ref "R35") (pin "1") (pinfunction "1_1") (pintype "passive"))
    )
    (net (code "8") (name "ADC_TIMBRE") (class "Default")
      (node (ref "C47") (pin "2") (pinfunction "2_2") (pintype "passive"))
      (node (ref "IC4") (pin "20") (pinfunction "PB2/SDADC1_AIN4P/SDADC2_AIN6P_20") (pintype "bidirectional"))
      (node (ref "IC6") (pin "8") (pinfunction "OUT_8") (pintype "output"))
      (node (ref "R32") (pin "1") (pinfunction "1_1") (pintype "passive"))
    )
    (net (code "9") (name "ADC_TRIG") (class "Default")
      (node (ref "C38") (pin "2") (pinfunction "2_2") (pintype "passive"))
      (node (ref "IC4") (pin "18") (pinfunction "PB0/SPI1_MOSI/I2S1_SD/TIM3_CH3/ADC_IN8/SDADC1_AIN6P_18") (pintype "bidirectional"))
      (node (ref "IC6") (pin "1") (pinfunction "OUT_1") (pintype "output"))
      (node (ref "R17") (pin "1") (pinfunction "1_1") (pintype "passive"))
    )
    (net (code "10") (name "ADC_V_OCT") (class "Default")
      (node (ref "C48") (pin "2") (pinfunction "2_2") (pintype "passive"))
      (node (ref "IC4") (pin "26") (pinfunction "PB14/SPI2_MISO/I2S2_MCK/USART3_RTS/SDADC3_AIN8P_26") (pintype "bidirectional"))
      (node (ref "IC7") (pin "7") (pinfunction "OUT_7") (pintype "output"))
      (node (ref "R34") (pin "1") (pinfunction "1_1") (pintype "passive"))
    )
    (net (code "11") (name "AREF_-10") (class "Default")
      (node (ref "C50") (pin "1") (pinfunction "1_1") (pintype "passive"))
      (node (ref "IC9") (pin "2") (pinfunction "A_2") (pintype "passive"))
      (node (ref "R23") (pin "2") (pinfunction "2_2") (pintype "passive"))
      (node (ref "R25") (pin "2") (pinfunction "2_2") (pintype "passive"))
      (node (ref "R26") (pin "2") (pinfunction "2_2") (pintype "passive"))
      (node (ref "R27") (pin "2") (pinfunction "2_2") (pintype "passive"))
      (node (ref "R29") (pin "2") (pinfunction "2_2") (pintype "passive"))
      (node (ref "R30") (pin "2") (pinfunction "2_2") (pintype "passive"))
      (node (ref "R33") (pin "2") (pinfunction "2_2") (pintype "passive"))
      (node (ref "R36") (pin "2") (pinfunction "2_2") (pintype "passive"))
      (node (ref "R37") (pin "2") (pinfunction "2_2") (pintype "passive"))
    )
    (net (code "12") (name "DAC_BCK") (class "Default")
      (node (ref "IC4") (pin "29") (pinfunction "PA8/SPI2_SCK/I2S2_CK/I2C2_SMBA/USART1_CK/TIM5_CH1_29") (pintype "bidirectional"))
      (node (ref "IC5") (pin "13") (pinfunction "BCK_13") (pintype "input"))
    )
    (net (code "13") (name "DAC_DIN") (class "Default")
      (node (ref "IC4") (pin "31") (pinfunction "PA10/SPI2_MOSI/I2S2_SD/I2C2_SDA/USART1_RX/TIM2_CH4_31") (pintype "bidirectional"))
      (node (ref "IC5") (pin "14") (pinfunction "DIN_14") (pintype "input"))
    )
    (net (code "14") (name "DAC_LRCK") (class "Default")
      (node (ref "IC4") (pin "32") (pinfunction "PA11/SPI2_NSS/I2S2_WS/SPI1_NSS/I2S1_WS/USART1_CTS/CAN_RX/TIM4_CH1/TIM5_CH2_32") (pintype "bidirectional"))
      (node (ref "IC5") (pin "15") (pinfunction "LRCK_15") (pintype "input"))
    )
    (net (code "15") (name "FREQ_ATT") (class "Default")
      (node (ref "FREQ_ATT") (pin "1") (pinfunction "1_1") (pintype "passive"))
      (node (ref "IC4") (pin "15") (pinfunction "PA5/SPI1_SCK/I2S1_CK/TIM2_CH1/ADC_IN5/DAC1_OUT2_15") (pintype "bidirectional"))
    )
    (net (code "16") (name "FREQ_POT") (class "Default")
      (node (ref "FREQ_POT") (pin "1") (pinfunction "1_1") (pintype "passive"))
      (node (ref "IC4") (pin "10") (pinfunction "PA0/USART2_CTS/TIM2_CH1/TIM5_CH1/ADC_IN0_10") (pintype "bidirectional"))
    )
    (net (code "17") (name "GND") (class "Default")
      (node (ref "C1") (pin "2") (pinfunction "2_2") (pintype "passive"))
      (node (ref "C10") (pin "2") (pinfunction "2_2") (pintype "passive"))
      (node (ref "C13") (pin "2") (pinfunction "2_2") (pintype "passive"))
      (node (ref "C14") (pin "1") (pinfunction "1_1") (pintype "passive"))
      (node (ref "C15") (pin "2") (pinfunction "2_2") (pintype "passive"))
      (node (ref "C16") (pin "-") (pinfunction "-_-") (pintype "passive"))
      (node (ref "C17") (pin "2") (pinfunction "2_2") (pintype "passive"))
      (node (ref "C18") (pin "2") (pinfunction "2_2") (pintype "passive"))
      (node (ref "C19") (pin "2") (pinfunction "2_2") (pintype "passive"))
      (node (ref "C2") (pin "2") (pinfunction "2_2") (pintype "passive"))
      (node (ref "C20") (pin "2") (pinfunction "2_2") (pintype "passive"))
      (node (ref "C21") (pin "1") (pinfunction "1_1") (pintype "passive"))
      (node (ref "C22") (pin "-") (pinfunction "-_-") (pintype "passive"))
      (node (ref "C23") (pin "2") (pinfunction "2_2") (pintype "passive"))
      (node (ref "C24") (pin "2") (pinfunction "2_2") (pintype "passive"))
      (node (ref "C25") (pin "2") (pinfunction "2_2") (pintype "passive"))
      (node (ref "C26") (pin "2") (pinfunction "2_2") (pintype "passive"))
      (node (ref "C27") (pin "2") (pinfunction "2_2") (pintype "passive"))
      (node (ref "C28") (pin "2") (pinfunction "2_2") (pintype "passive"))
      (node (ref "C3") (pin "-") (pinfunction "-_-") (pintype "passive"))
      (node (ref "C30") (pin "-") (pinfunction "-_-") (pintype "passive"))
      (node (ref "C31") (pin "2") (pinfunction "2_2") (pintype "passive"))
      (node (ref "C33") (pin "2") (pinfunction "2_2") (pintype "passive"))
      (node (ref "C35") (pin "2") (pinfunction "2_2") (pintype "passive"))
      (node (ref "C36") (pin "2") (pinfunction "2_2") (pintype "passive"))
      (node (ref "C37") (pin "2") (pinfunction "2_2") (pintype "passive"))
      (node (ref "C4") (pin "-") (pinfunction "-_-") (pintype "passive"))
      (node (ref "C44") (pin "2") (pinfunction "2_2") (pintype "passive"))
      (node (ref "C45") (pin "1") (pinfunction "1_1") (pintype "passive"))
      (node (ref "C5") (pin "+") (pinfunction "+_+") (pintype "passive"))
      (node (ref "C50") (pin "2") (pinfunction "2_2") (pintype "passive"))
      (node (ref "C54") (pin "2") (pinfunction "2_2") (pintype "passive"))
      (node (ref "C55") (pin "2") (pinfunction "2_2") (pintype "passive"))
      (node (ref "C56") (pin "2") (pinfunction "2_2") (pintype "passive"))
      (node (ref "C57") (pin "2") (pinfunction "2_2") (pintype "passive"))
      (node (ref "C58") (pin "2") (pinfunction "2_2") (pintype "passive"))
      (node (ref "C59") (pin "2") (pinfunction "2_2") (pintype "passive"))
      (node (ref "C6") (pin "2") (pinfunction "2_2") (pintype "passive"))
      (node (ref "C60") (pin "2") (pinfunction "2_2") (pintype "passive"))
      (node (ref "C61") (pin "2") (pinfunction "2_2") (pintype "passive"))
      (node (ref "C7") (pin "-") (pinfunction "-_-") (pintype "passive"))
      (node (ref "C8") (pin "2") (pinfunction "2_2") (pintype "passive"))
      (node (ref "C9") (pin "2") (pinfunction "2_2") (pintype "passive"))
      (node (ref "D3") (pin "1") (pinfunction "A_1") (pintype "passive"))
      (node (ref "GND_1") (pin "1") (pinfunction "1_1") (pintype "passive"))
      (node (ref "GND_2") (pin "1") (pinfunction "1_1") (pintype "passive"))
      (node (ref "IC1") (pin "2") (pinfunction "GND_2") (pintype "passive"))
      (node (ref "IC2") (pin "1") (pinfunction "GND_1") (pintype "bidirectional"))
      (node (ref "IC2") (pin "21") (pinfunction "BLANK_21") (pintype "bidirectional"))
      (node (ref "IC3") (pin "2") (pinfunction "GND_2") (pintype "passive"))
      (node (ref "IC4") (pin "23") (pinfunction "VSSSD/VREFSD-_23") (pintype "power_in"))
      (node (ref "IC4") (pin "44") (pinfunction "BOOT0_44") (pintype "bidirectional"))
      (node (ref "IC4") (pin "47") (pinfunction "VSS_1_47") (pintype "power_in"))
      (node (ref "IC4") (pin "8") (pinfunction "VSSA_8") (pintype "power_in"))
      (node (ref "IC5") (pin "10") (pinfunction "DEMP_10") (pintype "input"))
      (node (ref "IC5") (pin "12") (pinfunction "SCK_12") (pintype "input"))
      (node (ref "IC5") (pin "16") (pinfunction "FMT_16") (pintype "input"))
      (node (ref "IC5") (pin "19") (pinfunction "DGND_19") (pintype "power_in"))
      (node (ref "IC5") (pin "3") (pinfunction "CPGND_3") (pintype "bidirectional"))
      (node (ref "IC5") (pin "9") (pinfunction "AGND_9") (pintype "power_in"))
      (node (ref "IC6") (pin "10") (pinfunction "+IN_10") (pintype "input"))
      (node (ref "IC6") (pin "11") (pinfunction "V-_11") (pintype "power_in"))
      (node (ref "IC6") (pin "12") (pinfunction "+IN_12") (pintype "input"))
      (node (ref "IC6") (pin "3") (pinfunction "+IN_3") (pintype "input"))
      (node (ref "IC6") (pin "5") (pinfunction "+IN_5") (pintype "input"))
      (node (ref "IC7") (pin "10") (pinfunction "+IN_10") (pintype "input"))
      (node (ref "IC7") (pin "11") (pinfunction "V-_11") (pintype "power_in"))
      (node (ref "IC7") (pin "12") (pinfunction "+IN_12") (pintype "input"))
      (node (ref "IC7") (pin "3") (pinfunction "+IN_3") (pintype "input"))
      (node (ref "IC7") (pin "5") (pinfunction "+IN_5") (pintype "input"))
      (node (ref "IC8") (pin "3") (pinfunction "+IN_3") (pintype "input"))
      (node (ref "IC8") (pin "5") (pinfunction "+IN_5") (pintype "input"))
      (node (ref "IC9") (pin "1") (pinfunction "C_1") (pintype "passive"))
      (node (ref "JP6") (pin "1") (pinfunction "1_1") (pintype "passive"))
      (node (ref "JP8") (pin "3") (pinfunction "3_3") (pintype "passive"))
      (node (ref "JP8") (pin "4") (pinfunction "4_4") (pintype "passive"))
      (node (ref "JP8") (pin "5") (pinfunction "5_5") (pintype "passive"))
      (node (ref "JP8") (pin "6") (pinfunction "6_6") (pintype "passive"))
      (node (ref "JP8") (pin "7") (pinfunction "7_7") (pintype "passive"))
      (node (ref "JP8") (pin "8") (pinfunction "8_8") (pintype "passive"))
      (node (ref "Q1") (pin "2") (pinfunction "LID1_2") (pintype "power_in"))
      (node (ref "Q1") (pin "4") (pinfunction "LID2_4") (pintype "power_in"))
      (node (ref "R3") (pin "2") (pinfunction "2_2") (pintype "passive"))
    )
    (net (code "18") (name "HARMONICS_POT") (class "Default")
      (node (ref "HARMONICS_POT") (pin "1") (pinfunction "1_1") (pintype "passive"))
      (node (ref "IC4") (pin "12") (pinfunction "PA2/SPI3_MISO/I2S3_MCK/USART2_TX/TIM2_CH3/TIM5_CH3/ADC_IN2_12") (pintype "bidirectional"))
    )
    (net (code "19") (name "LEDS_SCK") (class "Default")
      (node (ref "IC2") (pin "3") (pinfunction "SCLK_3") (pintype "bidirectional"))
      (node (ref "IC4") (pin "33") (pinfunction "PA12/SPI1_SCK/I2S1_CK/USART1_RTS/CAN_TX/TIM4_CH2/TIM5_CH3_33") (pintype "bidirectional"))
    )
    (net (code "20") (name "LEDS_SIN") (class "Default")
      (node (ref "IC2") (pin "2") (pinfunction "SIN_2") (pintype "bidirectional"))
      (node (ref "IC4") (pin "35") (pinfunction "PF6/SPI1_MOSI/I2S1_SD/USART3_RTS/TIM4_CH4/I2C2_SCL_35") (pintype "bidirectional"))
    )
    (net (code "21") (name "LEDS_SS") (class "Default")
      (node (ref "IC2") (pin "4") (pinfunction "LAT_4") (pintype "bidirectional"))
      (node (ref "IC4") (pin "36") (pinfunction "PF7/I2C2_SDA/USART2_CK_36") (pintype "bidirectional"))
    )
    (net (code "22") (name "MORPH_ATT") (class "Default")
      (node (ref "IC4") (pin "14") (pinfunction "PA4/SPI1_NSS/I2S1_WS/SPI3_NSS/I2S3_WS/USART2_CK/TIM3_CH2/ADC_IN4/DAC1_OUT1_14") (pintype "bidirectional"))
      (node (ref "MORPH_ATT") (pin "1") (pinfunction "1_1") (pintype "passive"))
    )
    (net (code "23") (name "MORPH_POT") (class "Default")
      (node (ref "IC4") (pin "11") (pinfunction "PA1/SPI3_SCK/I2S3_CK/USART2_RTS/TIM2_CH2/TIM5_CH2/ADC_IN1_11") (pintype "bidirectional"))
      (node (ref "MORPH_POT") (pin "1") (pinfunction "1_1") (pintype "passive"))
    )
    (net (code "24") (name "NORMALIZATION_PROBE") (class "Default")
      (node (ref "D3") (pin "3") (pinfunction "AC_3") (pintype "passive"))
      (node (ref "IC4") (pin "30") (pinfunction "PA9/SPI_MISO/I2S2_MCK/I2C2_SCL/USART1_TX/TIM2_CH3_30") (pintype "bidirectional"))
      (node (ref "TO_BAT") (pin "1") (pinfunction "1_1") (pintype "passive"))
    )
    (net (code "25") (name "Net-(C2-Pad1)") (class "Default")
      (node (ref "C2") (pin "1") (pinfunction "1_1") (pintype "passive"))
      (node (ref "D1") (pin "C") (pinfunction "C_C") (pintype "passive"))
      (node (ref "L1") (pin "1") (pinfunction "1_1") (pintype "passive"))
      (node (ref "L2") (pin "2") (pinfunction "2_2") (pintype "passive"))
      (node (ref "L5") (pin "2") (pinfunction "2_2") (pintype "passive"))
    )
    (net (code "26") (name "Net-(C21-Pad2)") (class "Default")
      (node (ref "C21") (pin "2") (pinfunction "2_2") (pintype "passive"))
      (node (ref "Q1") (pin "1") (pinfunction "1_1") (pintype "passive"))
      (node (ref "R6") (pin "2") (pinfunction "2_2") (pintype "passive"))
    )
    (net (code "27") (name "Net-(C33-Pad1)") (class "Default")
      (node (ref "C33") (pin "1") (pinfunction "1_1") (pintype "passive"))
      (node (ref "R11") (pin "1") (pinfunction "1_1") (pintype "passive"))
      (node (ref "R21") (pin "2") (pinfunction "2_2") (pintype "passive"))
    )
    (net (code "28") (name "Net-(C35-Pad1)") (class "Default")
      (node (ref "C35") (pin "1") (pinfunction "1_1") (pintype "passive"))
      (node (ref "R12") (pin "1") (pinfunction "1_1") (pintype "passive"))
      (node (ref "R16") (pin "2") (pinfunction "2_2") (pintype "passive"))
    )
    (net (code "29") (name "Net-(C54-Pad1)") (class "Default")
      (node (ref "C54") (pin "1") (pinfunction "1_1") (pintype "passive"))
      (node (ref "R39") (pin "2") (pinfunction "2_2") (pintype "passive"))
      (node (ref "TO_IC7C") (pin "1") (pinfunction "1_1") (pintype "passive"))
    )
    (net (code "30") (name "Net-(C55-Pad1)") (class "Default")
      (node (ref "C55") (pin "1") (pinfunction "1_1") (pintype "passive"))
      (node (ref "R40") (pin "2") (pinfunction "2_2") (pintype "passive"))
      (node (ref "TO_IC6B") (pin "1") (pinfunction "1_1") (pintype "passive"))
    )
    (net (code "31") (name "Net-(C56-Pad1)") (class "Default")
      (node (ref "C56") (pin "1") (pinfunction "1_1") (pintype "passive"))
      (node (ref "R41") (pin "2") (pinfunction "2_2") (pintype "passive"))
      (node (ref "TO_IC6C") (pin "1") (pinfunction "1_1") (pintype "passive"))
    )
    (net (code "32") (name "Net-(C57-Pad1)") (class "Default")
      (node (ref "C57") (pin "1") (pinfunction "1_1") (pintype "passive"))
      (node (ref "R15") (pin "2") (pinfunction "2_2") (pintype "passive"))
      (node (ref "TO_IC7A") (pin "1") (pinfunction "1_1") (pintype "passive"))
    )
    (net (code "33") (name "Net-(C58-Pad1)") (class "Default")
      (node (ref "C58") (pin "1") (pinfunction "1_1") (pintype "passive"))
      (node (ref "R13") (pin "2") (pinfunction "2_2") (pintype "passive"))
      (node (ref "TO_IC7D") (pin "1") (pinfunction "1_1") (pintype "passive"))
    )
    (net (code "34") (name "Net-(C59-Pad1)") (class "Default")
      (node (ref "C59") (pin "1") (pinfunction "1_1") (pintype "passive"))
      (node (ref "R24") (pin "2") (pinfunction "2_2") (pintype "passive"))
      (node (ref "TO_IC6A") (pin "1") (pinfunction "1_1") (pintype "passive"))
    )
    (net (code "35") (name "Net-(C60-Pad1)") (class "Default")
      (node (ref "C60") (pin "1") (pinfunction "1_1") (pintype "passive"))
      (node (ref "R38") (pin "2") (pinfunction "2_2") (pintype "passive"))
      (node (ref "TO_IC7B") (pin "1") (pinfunction "1_1") (pintype "passive"))
    )
    (net (code "36") (name "Net-(C61-Pad1)") (class "Default")
      (node (ref "C61") (pin "1") (pinfunction "1_1") (pintype "passive"))
      (node (ref "R14") (pin "2") (pinfunction "2_2") (pintype "passive"))
      (node (ref "TO_IC6D") (pin "1") (pinfunction "1_1") (pintype "passive"))
    )
    (net (code "37") (name "Net-(D1-PadA)") (class "Default")
      (node (ref "D1") (pin "A") (pinfunction "A_A") (pintype "passive"))
      (node (ref "JP8") (pin "10") (pinfunction "10_10") (pintype "passive"))
      (node (ref "JP8") (pin "9") (pinfunction "9_9") (pintype "passive"))
    )
    (net (code "38") (name "Net-(D2-PadA)") (class "Default")
      (node (ref "D2") (pin "A") (pinfunction "A_A") (pintype "passive"))
      (node (ref "L3") (pin "2") (pinfunction "2_2") (pintype "passive"))
    )
    (net (code "39") (name "Net-(D2-PadC)") (class "Default")
      (node (ref "D2") (pin "C") (pinfunction "C_C") (pintype "passive"))
      (node (ref "JP8") (pin "1") (pinfunction "1_1") (pintype "passive"))
      (node (ref "JP8") (pin "2") (pinfunction "2_2") (pintype "passive"))
    )
    (net (code "40") (name "Net-(IC1-VI)") (class "Default")
      (node (ref "C1") (pin "1") (pinfunction "1_1") (pintype "passive"))
      (node (ref "IC1") (pin "1") (pinfunction "VI_1") (pintype "input"))
      (node (ref "L1") (pin "2") (pinfunction "2_2") (pintype "passive"))
    )
    (net (code "41") (name "Net-(IC2-IREF)") (class "Default")
      (node (ref "IC2") (pin "23") (pinfunction "IREF_23") (pintype "bidirectional"))
      (node (ref "R3") (pin "1") (pinfunction "1_1") (pintype "passive"))
    )
    (net (code "42") (name "Net-(IC2-OUT0)") (class "Default")
      (node (ref "IC2") (pin "5") (pinfunction "OUT0_5") (pintype "bidirectional"))
      (node (ref "LED5_R") (pin "1") (pinfunction "1_1") (pintype "passive"))
    )
    (net (code "43") (name "Net-(IC2-OUT1)") (class "Default")
      (node (ref "IC2") (pin "6") (pinfunction "OUT1_6") (pintype "bidirectional"))
      (node (ref "LED5_G") (pin "1") (pinfunction "1_1") (pintype "passive"))
    )
    (net (code "44") (name "Net-(IC2-OUT2)") (class "Default")
      (node (ref "IC2") (pin "7") (pinfunction "OUT2_7") (pintype "bidirectional"))
      (node (ref "LED6_R") (pin "1") (pinfunction "1_1") (pintype "passive"))
    )
    (net (code "45") (name "Net-(IC2-OUT3)") (class "Default")
      (node (ref "IC2") (pin "8") (pinfunction "OUT3_8") (pintype "bidirectional"))
      (node (ref "LED6_G") (pin "1") (pinfunction "1_1") (pintype "passive"))
    )
    (net (code "46") (name "Net-(IC2-OUT4)") (class "Default")
      (node (ref "IC2") (pin "9") (pinfunction "OUT4_9") (pintype "bidirectional"))
      (node (ref "LED7_R") (pin "1") (pinfunction "1_1") (pintype "passive"))
    )
    (net (code "47") (name "Net-(IC2-OUT5)") (class "Default")
      (node (ref "IC2") (pin "10") (pinfunction "OUT5_10") (pintype "bidirectional"))
      (node (ref "LED7_G") (pin "1") (pinfunction "1_1") (pintype "passive"))
    )
    (net (code "48") (name "Net-(IC2-OUT6)") (class "Default")
      (node (ref "IC2") (pin "11") (pinfunction "OUT6_11") (pintype "bidirectional"))
      (node (ref "LED8_R") (pin "1") (pinfunction "1_1") (pintype "passive"))
    )
    (net (code "49") (name "Net-(IC2-OUT7)") (class "Default")
      (node (ref "IC2") (pin "12") (pinfunction "OUT7_12") (pintype "bidirectional"))
      (node (ref "LED8_G") (pin "1") (pinfunction "1_1") (pintype "passive"))
    )
    (net (code "50") (name "Net-(IC2-OUT8)") (class "Default")
      (node (ref "IC2") (pin "13") (pinfunction "OUT8_13") (pintype "bidirectional"))
      (node (ref "LED4_R") (pin "1") (pinfunction "1_1") (pintype "passive"))
    )
    (net (code "51") (name "Net-(IC2-OUT9)") (class "Default")
      (node (ref "IC2") (pin "14") (pinfunction "OUT9_14") (pintype "bidirectional"))
      (node (ref "LED4_G") (pin "1") (pinfunction "1_1") (pintype "passive"))
    )
    (net (code "52") (name "Net-(IC2-OUT10)") (class "Default")
      (node (ref "IC2") (pin "15") (pinfunction "OUT10_15") (pintype "bidirectional"))
      (node (ref "LED3_R") (pin "1") (pinfunction "1_1") (pintype "passive"))
    )
    (net (code "53") (name "Net-(IC2-OUT11)") (class "Default")
      (node (ref "IC2") (pin "16") (pinfunction "OUT11_16") (pintype "bidirectional"))
      (node (ref "LED3_G") (pin "1") (pinfunction "1_1") (pintype "passive"))
    )
    (net (code "54") (name "Net-(IC2-OUT12)") (class "Default")
      (node (ref "IC2") (pin "17") (pinfunction "OUT12_17") (pintype "bidirectional"))
      (node (ref "LED2_R") (pin "1") (pinfunction "1_1") (pintype "passive"))
    )
    (net (code "55") (name "Net-(IC2-OUT13)") (class "Default")
      (node (ref "IC2") (pin "18") (pinfunction "OUT13_18") (pintype "bidirectional"))
      (node (ref "LED2_G") (pin "1") (pinfunction "1_1") (pintype "passive"))
    )
    (net (code "56") (name "Net-(IC2-OUT14)") (class "Default")
      (node (ref "IC2") (pin "19") (pinfunction "OUT14_19") (pintype "bidirectional"))
      (node (ref "LED1_R") (pin "1") (pinfunction "1_1") (pintype "passive"))
    )
    (net (code "57") (name "Net-(IC2-OUT15)") (class "Default")
      (node (ref "IC2") (pin "20") (pinfunction "OUT15_20") (pintype "bidirectional"))
      (node (ref "LED1_G") (pin "1") (pinfunction "1_1") (pintype "passive"))
    )
    (net (code "58") (name "Net-(IC2-VCC)") (class "Default")
      (node (ref "C7") (pin "+") (pinfunction "+_+") (pintype "passive"))
      (node (ref "C8") (pin "1") (pinfunction "1_1") (pintype "passive"))
      (node (ref "IC2") (pin "24") (pinfunction "VCC_24") (pintype "bidirectional"))
      (node (ref "L4") (pin "1") (pinfunction "1_1") (pintype "passive"))
    )
    (net (code "59") (name "Net-(IC3-VI)") (class "Default")
      (node (ref "C13") (pin "1") (pinfunction "1_1") (pintype "passive"))
      (node (ref "IC3") (pin "3") (pinfunction "VI_3") (pintype "input"))
      (node (ref "L5") (pin "1") (pinfunction "1_1") (pintype "passive"))
    )
    (net (code "60") (name "Net-(IC4-PF0{slash}OSC_IN{slash}I2C2_SDA)") (class "Default")
      (node (ref "IC4") (pin "5") (pinfunction "PF0/OSC_IN/I2C2_SDA_5") (pintype "bidirectional"))
      (node (ref "R5") (pin "1") (pinfunction "1_1") (pintype "passive"))
    )
    (net (code "61") (name "Net-(IC4-PF1{slash}OSC_OUT{slash}I2C2_SCL)") (class "Default")
      (node (ref "IC4") (pin "6") (pinfunction "PF1/OSC_OUT/I2C2_SCL_6") (pintype "bidirectional"))
      (node (ref "R6") (pin "1") (pinfunction "1_1") (pintype "passive"))
    )
    (net (code "62") (name "Net-(IC5-CAPM)") (class "Default")
      (node (ref "C29") (pin "2") (pinfunction "2_2") (pintype "passive"))
      (node (ref "IC5") (pin "4") (pinfunction "CAPM_4") (pintype "bidirectional"))
    )
    (net (code "63") (name "Net-(IC5-CAPP)") (class "Default")
      (node (ref "C29") (pin "1") (pinfunction "1_1") (pintype "passive"))
      (node (ref "IC5") (pin "2") (pinfunction "CAPP_2") (pintype "bidirectional"))
    )
    (net (code "64") (name "Net-(IC5-LDOO)") (class "Default")
      (node (ref "C18") (pin "1") (pinfunction "1_1") (pintype "passive"))
      (node (ref "IC5") (pin "18") (pinfunction "LDOO_18") (pintype "bidirectional"))
    )
    (net (code "65") (name "Net-(IC5-OUTL)") (class "Default")
      (node (ref "IC5") (pin "6") (pinfunction "OUTL_6") (pintype "output"))
      (node (ref "R11") (pin "2") (pinfunction "2_2") (pintype "passive"))
    )
    (net (code "66") (name "Net-(IC5-OUTR)") (class "Default")
      (node (ref "IC5") (pin "7") (pinfunction "OUTR_7") (pintype "output"))
      (node (ref "R12") (pin "2") (pinfunction "2_2") (pintype "passive"))
    )
    (net (code "67") (name "Net-(IC5-VNEG)") (class "Default")
      (node (ref "C31") (pin "1") (pinfunction "1_1") (pintype "passive"))
      (node (ref "IC5") (pin "5") (pinfunction "VNEG_5") (pintype "input"))
    )
    (net (code "68") (name "Net-(IC6A--IN)") (class "Default")
      (node (ref "C38") (pin "1") (pinfunction "1_1") (pintype "passive"))
      (node (ref "IC6") (pin "2") (pinfunction "-IN_2") (pintype "input"))
      (node (ref "R17") (pin "2") (pinfunction "2_2") (pintype "passive"))
      (node (ref "R24") (pin "1") (pinfunction "1_1") (pintype "passive"))
      (node (ref "R25") (pin "1") (pinfunction "1_1") (pintype "passive"))
    )
    (net (code "69") (name "Net-(IC6B--IN)") (class "Default")
      (node (ref "C46") (pin "1") (pinfunction "1_1") (pintype "passive"))
      (node (ref "IC6") (pin "6") (pinfunction "-IN_6") (pintype "input"))
      (node (ref "R30") (pin "1") (pinfunction "1_1") (pintype "passive"))
      (node (ref "R31") (pin "2") (pinfunction "2_2") (pintype "passive"))
      (node (ref "R40") (pin "1") (pinfunction "1_1") (pintype "passive"))
    )
    (net (code "70") (name "Net-(IC6C--IN)") (class "Default")
      (node (ref "C47") (pin "1") (pinfunction "1_1") (pintype "passive"))
      (node (ref "IC6") (pin "9") (pinfunction "-IN_9") (pintype "input"))
      (node (ref "R32") (pin "2") (pinfunction "2_2") (pintype "passive"))
      (node (ref "R33") (pin "1") (pinfunction "1_1") (pintype "passive"))
      (node (ref "R41") (pin "1") (pinfunction "1_1") (pintype "passive"))
    )
    (net (code "71") (name "Net-(IC6D--IN)") (class "Default")
      (node (ref "C39") (pin "1") (pinfunction "1_1") (pintype "passive"))
      (node (ref "IC6") (pin "13") (pinfunction "-IN_13") (pintype "input"))
      (node (ref "R14") (pin "1") (pinfunction "1_1") (pintype "passive"))
      (node (ref "R18") (pin "2") (pinfunction "2_2") (pintype "passive"))
      (node (ref "R26") (pin "1") (pinfunction "1_1") (pintype "passive"))
    )
    (net (code "72") (name "Net-(IC7A--IN)") (class "Default")
      (node (ref "C40") (pin "1") (pinfunction "1_1") (pintype "passive"))
      (node (ref "IC7") (pin "2") (pinfunction "-IN_2") (pintype "input"))
      (node (ref "R15") (pin "1") (pinfunction "1_1") (pintype "passive"))
      (node (ref "R19") (pin "2") (pinfunction "2_2") (pintype "passive"))
      (node (ref "R23") (pin "1") (pinfunction "1_1") (pintype "passive"))
    )
    (net (code "73") (name "Net-(IC7B--IN)") (class "Default")
      (node (ref "C48") (pin "1") (pinfunction "1_1") (pintype "passive"))
      (node (ref "IC7") (pin "6") (pinfunction "-IN_6") (pintype "input"))
      (node (ref "R29") (pin "1") (pinfunction "1_1") (pintype "passive"))
      (node (ref "R34") (pin "2") (pinfunction "2_2") (pintype "passive"))
      (node (ref "R38") (pin "1") (pinfunction "1_1") (pintype "passive"))
    )
    (net (code "74") (name "Net-(IC7C--IN)") (class "Default")
      (node (ref "C49") (pin "1") (pinfunction "1_1") (pintype "passive"))
      (node (ref "IC7") (pin "9") (pinfunction "-IN_9") (pintype "input"))
      (node (ref "R35") (pin "2") (pinfunction "2_2") (pintype "passive"))
      (node (ref "R36") (pin "1") (pinfunction "1_1") (pintype "passive"))
      (node (ref "R39") (pin "1") (pinfunction "1_1") (pintype "passive"))
    )
    (net (code "75") (name "Net-(IC7D--IN)") (class "Default")
      (node (ref "C41") (pin "1") (pinfunction "1_1") (pintype "passive"))
      (node (ref "IC7") (pin "13") (pinfunction "-IN_13") (pintype "input"))
      (node (ref "R13") (pin "1") (pinfunction "1_1") (pintype "passive"))
      (node (ref "R20") (pin "2") (pinfunction "2_2") (pintype "passive"))
      (node (ref "R27") (pin "1") (pinfunction "1_1") (pintype "passive"))
    )
    (net (code "76") (name "Net-(IC8A--IN)") (class "Default")
      (node (ref "C42") (pin "1") (pinfunction "1_1") (pintype "passive"))
      (node (ref "IC8") (pin "2") (pinfunction "-IN_2") (pintype "input"))
      (node (ref "R21") (pin "1") (pinfunction "1_1") (pintype "passive"))
      (node (ref "R22") (pin "2") (pinfunction "2_2") (pintype "passive"))
    )
    (net (code "77") (name "Net-(IC8A-OUT)") (class "Default")
      (node (ref "C42") (pin "2") (pinfunction "2_2") (pintype "passive"))
      (node (ref "IC8") (pin "1") (pinfunction "OUT_1") (pintype "output"))
      (node (ref "R22") (pin "1") (pinfunction "1_1") (pintype "passive"))
      (node (ref "R46") (pin "2") (pinfunction "2_2") (pintype "passive"))
    )
    (net (code "78") (name "Net-(IC8B--IN)") (class "Default")
      (node (ref "C43") (pin "1") (pinfunction "1_1") (pintype "passive"))
      (node (ref "IC8") (pin "6") (pinfunction "-IN_6") (pintype "input"))
      (node (ref "R16") (pin "1") (pinfunction "1_1") (pintype "passive"))
      (node (ref "R28") (pin "2") (pinfunction "2_2") (pintype "passive"))
    )
    (net (code "79") (name "Net-(IC8B-OUT)") (class "Default")
      (node (ref "C43") (pin "2") (pinfunction "2_2") (pintype "passive"))
      (node (ref "IC8") (pin "7") (pinfunction "OUT_7") (pintype "output"))
      (node (ref "R28") (pin "1") (pinfunction "1_1") (pintype "passive"))
      (node (ref "R47") (pin "2") (pinfunction "2_2") (pintype "passive"))
    )
    (net (code "80") (name "Net-(JP5-Pad1)") (class "Default")
      (node (ref "JP5") (pin "1") (pinfunction "1_1") (pintype "passive"))
      (node (ref "R9") (pin "1") (pinfunction "1_1") (pintype "passive"))
    )
    (net (code "81") (name "Net-(JP5-Pad2)") (class "Default")
      (node (ref "JP5") (pin "2") (pinfunction "2_2") (pintype "passive"))
      (node (ref "R10") (pin "1") (pinfunction "1_1") (pintype "passive"))
    )
    (net (code "82") (name "Net-(Q1B-2)") (class "Default")
      (node (ref "C14") (pin "2") (pinfunction "2_2") (pintype "passive"))
      (node (ref "Q1") (pin "3") (pinfunction "2_3") (pintype "passive"))
      (node (ref "R5") (pin "2") (pinfunction "2_2") (pintype "passive"))
    )
    (net (code "83") (name "Net-(R46-Pad1)") (class "Default")
      (node (ref "R46") (pin "1") (pinfunction "1_1") (pintype "passive"))
      (node (ref "TO_IC8A") (pin "1") (pinfunction "1_1") (pintype "passive"))
    )
    (net (code "84") (name "Net-(R47-Pad1)") (class "Default")
      (node (ref "R47") (pin "1") (pinfunction "1_1") (pintype "passive"))
      (node (ref "TO_IC8B") (pin "1") (pinfunction "1_1") (pintype "passive"))
    )
    (net (code "85") (name "RESET") (class "Default")
      (node (ref "C15") (pin "1") (pinfunction "1_1") (pintype "passive"))
      (node (ref "IC4") (pin "7") (pinfunction "NRST_7") (pintype "bidirectional"))
      (node (ref "JP6") (pin "4") (pinfunction "4_4") (pintype "passive"))
      (node (ref "R4") (pin "2") (pinfunction "2_2") (pintype "passive"))
    )
    (net (code "86") (name "RX") (class "Default")
      (node (ref "IC4") (pin "46") (pinfunction "PB9/SPI2_NSS/I2S2_WS/I2C1_SDA/USART3_RX/CAN_TX/TIM4_CH4_46") (pintype "bidirectional"))
      (node (ref "R9") (pin "2") (pinfunction "2_2") (pintype "passive"))
    )
    (net (code "87") (name "SWCLK") (class "Default")
      (node (ref "IC4") (pin "37") (pinfunction "PA14/I2C1_SDA/JTCK-SWCLK_37") (pintype "bidirectional"))
      (node (ref "JP6") (pin "3") (pinfunction "3_3") (pintype "passive"))
    )
    (net (code "88") (name "SWDIO") (class "Default")
      (node (ref "IC4") (pin "34") (pinfunction "PA13/SPI1_MISO/I2S1_MCK/USART3_CTS/TIM4_CH3/TIM5_CH4/JTMS-SWDIO_34") (pintype "bidirectional"))
      (node (ref "JP6") (pin "2") (pinfunction "2_2") (pintype "passive"))
    )
    (net (code "89") (name "SW_1") (class "Default")
      (node (ref "IC4") (pin "43") (pinfunction "PB7/I2C1_SDA/USART1_RX/TIM4_CH2_43") (pintype "bidirectional"))
      (node (ref "SW1") (pin "1") (pinfunction "1_1") (pintype "passive"))
    )
    (net (code "90") (name "SW_2") (class "Default")
      (node (ref "IC4") (pin "42") (pinfunction "PB6/I2C1_SCL/USART1_TX/TIM4_CH1_42") (pintype "bidirectional"))
      (node (ref "SW2") (pin "1") (pinfunction "1_1") (pintype "passive"))
    )
    (net (code "91") (name "TIMBRE_ATT") (class "Default")
      (node (ref "IC4") (pin "16") (pinfunction "PA6/SPI1_MISO/I2S1_MCK/TIM3_CH1/ADC_IN6/DAC2_OUT1_16") (pintype "bidirectional"))
      (node (ref "TIMBRE_ATT") (pin "1") (pinfunction "1_1") (pintype "passive"))
    )
    (net (code "92") (name "TIMBRE_POT") (class "Default")
      (node (ref "IC4") (pin "13") (pinfunction "PA3/SPI3_MOSI/I2S3_SD/USART2_RX/TIM2_CH4/TIM5_CH4/ADC_IN3_13") (pintype "bidirectional"))
      (node (ref "TIMBRE_POT") (pin "1") (pinfunction "1_1") (pintype "passive"))
    )
    (net (code "93") (name "TX") (class "Default")
      (node (ref "IC4") (pin "45") (pinfunction "PB8/SPI2_SCK/I2S2_CK/I2C1_SCL/USART3_TX/CAN_RX/TIM4_CH3_45") (pintype "bidirectional"))
      (node (ref "R10") (pin "2") (pinfunction "2_2") (pintype "passive"))
    )
    (net (code "94") (name "VCC") (class "Default")
      (node (ref "C37") (pin "1") (pinfunction "1_1") (pintype "passive"))
      (node (ref "C4") (pin "+") (pinfunction "+_+") (pintype "passive"))
      (node (ref "IC8") (pin "8") (pinfunction "V+_8") (pintype "power_in"))
      (node (ref "L2") (pin "1") (pinfunction "1_1") (pintype "passive"))
    )
    (net (code "95") (name "VEE") (class "Default")
      (node (ref "C45") (pin "2") (pinfunction "2_2") (pintype "passive"))
      (node (ref "C5") (pin "-") (pinfunction "-_-") (pintype "passive"))
      (node (ref "IC8") (pin "4") (pinfunction "V-_4") (pintype "power_in"))
      (node (ref "L3") (pin "1") (pinfunction "1_1") (pintype "passive"))
      (node (ref "R37") (pin "1") (pinfunction "1_1") (pintype "passive"))
    )
    (net (code "96") (name "unconnected-(IC2-SOUT-Pad22)") (class "Default")
      (node (ref "IC2") (pin "22") (pinfunction "SOUT_22") (pintype "bidirectional"))
    )
    (net (code "97") (name "unconnected-(IC4-PA15{slash}SPI1_NSS{slash}I2S1_WS{slash}SPI3_NSS{slash}I2S3_WS{slash}I2C1_SCL{slash}TIM2_CH1_ETR{slash}JTDI-Pad38)") (class "Default")
      (node (ref "IC4") (pin "38") (pinfunction "PA15/SPI1_NSS/I2S1_WS/SPI3_NSS/I2S3_WS/I2C1_SCL/TIM2_CH1_ETR/JTDI_38") (pintype "bidirectional"))
    )
    (net (code "98") (name "unconnected-(IC4-PB3{slash}SPI1_SCK{slash}I2S1_CK{slash}SPI3_SCK{slash}I2S3_CK{slash}USART2_TX{slash}TIM2_CH2{slash}JTDO{slash}SPI3_SCK{slash}JTDO-Pad39)") (class "Default")
      (node (ref "IC4") (pin "39") (pinfunction "PB3/SPI1_SCK/I2S1_CK/SPI3_SCK/I2S3_CK/USART2_TX/TIM2_CH2/JTDO/SPI3_SCK/JTDO_39") (pintype "bidirectional"))
    )
    (net (code "99") (name "unconnected-(IC4-PB4{slash}SPI1_MISO{slash}I2S1_MCK{slash}SPI3_MISO{slash}I2S3_MCK{slash}USART2_RX{slash}TIM3_CH1{slash}NJTRST-Pad40)") (class "Default")
      (node (ref "IC4") (pin "40") (pinfunction "PB4/SPI1_MISO/I2S1_MCK/SPI3_MISO/I2S3_MCK/USART2_RX/TIM3_CH1/NJTRST_40") (pintype "bidirectional"))
    )
    (net (code "100") (name "unconnected-(IC4-PB5{slash}SPI1_MOSI{slash}I2S1_SD{slash}SPI3_MOSI{slash}I2S3_SD{slash}I2C1_SMBAI{slash}USART2_CK{slash}TIM3_CH2-Pad41)") (class "Default")
      (node (ref "IC4") (pin "41") (pinfunction "PB5/SPI1_MOSI/I2S1_SD/SPI3_MOSI/I2S3_SD/I2C1_SMBAI/USART2_CK/TIM3_CH2_41") (pintype "bidirectional"))
    )
    (net (code "101") (name "unconnected-(IC4-PC13{slash}TIMESTAMP{slash}RTC_TAMPER1-Pad2)") (class "Default")
      (node (ref "IC4") (pin "2") (pinfunction "PC13/TIMESTAMP/RTC_TAMPER1_2") (pintype "bidirectional"))
    )
    (net (code "102") (name "unconnected-(IC4-PC14{slash}OSC32_IN-Pad3)") (class "Default")
      (node (ref "IC4") (pin "3") (pinfunction "PC14/OSC32_IN_3") (pintype "bidirectional"))
    )
    (net (code "103") (name "unconnected-(IC4-PC15{slash}OSC32_OUT-Pad4)") (class "Default")
      (node (ref "IC4") (pin "4") (pinfunction "PC15/OSC32_OUT_4") (pintype "bidirectional"))
    )
  )
)
